# HTMD-PREAMP2.net
KiCad netlist of a schematic drawn in Altium Designer
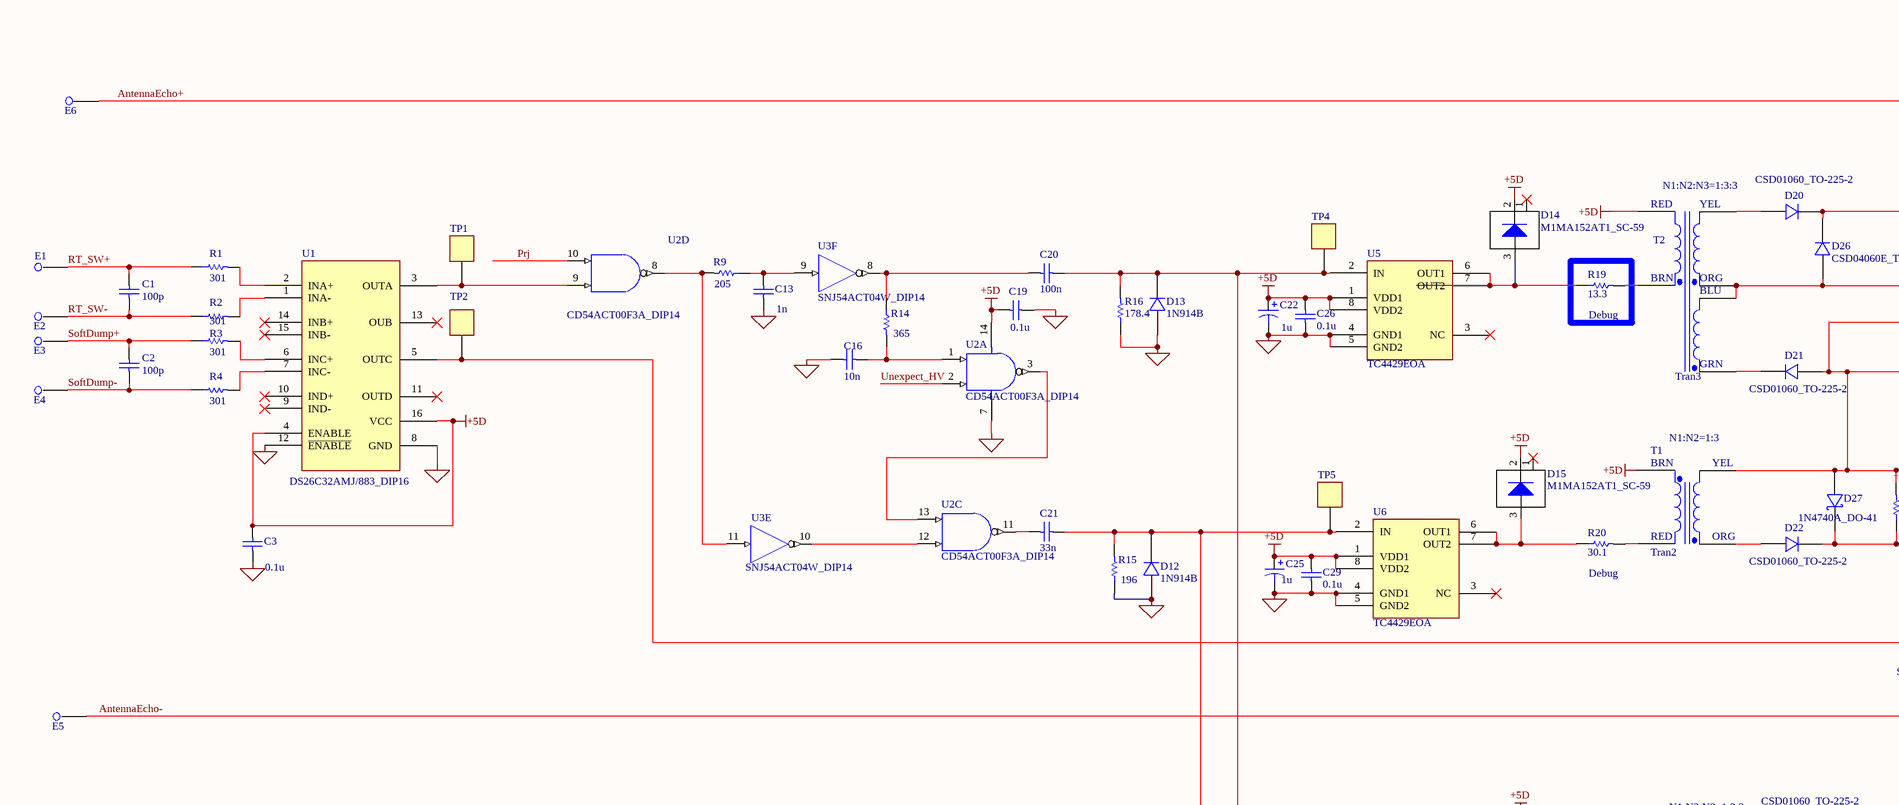
[diagram p0: HTMD-PREAMP2.SCHDOC, top left]
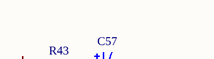
[diagram p1: HTMD-PREAMP2.SCHDOC, top right]
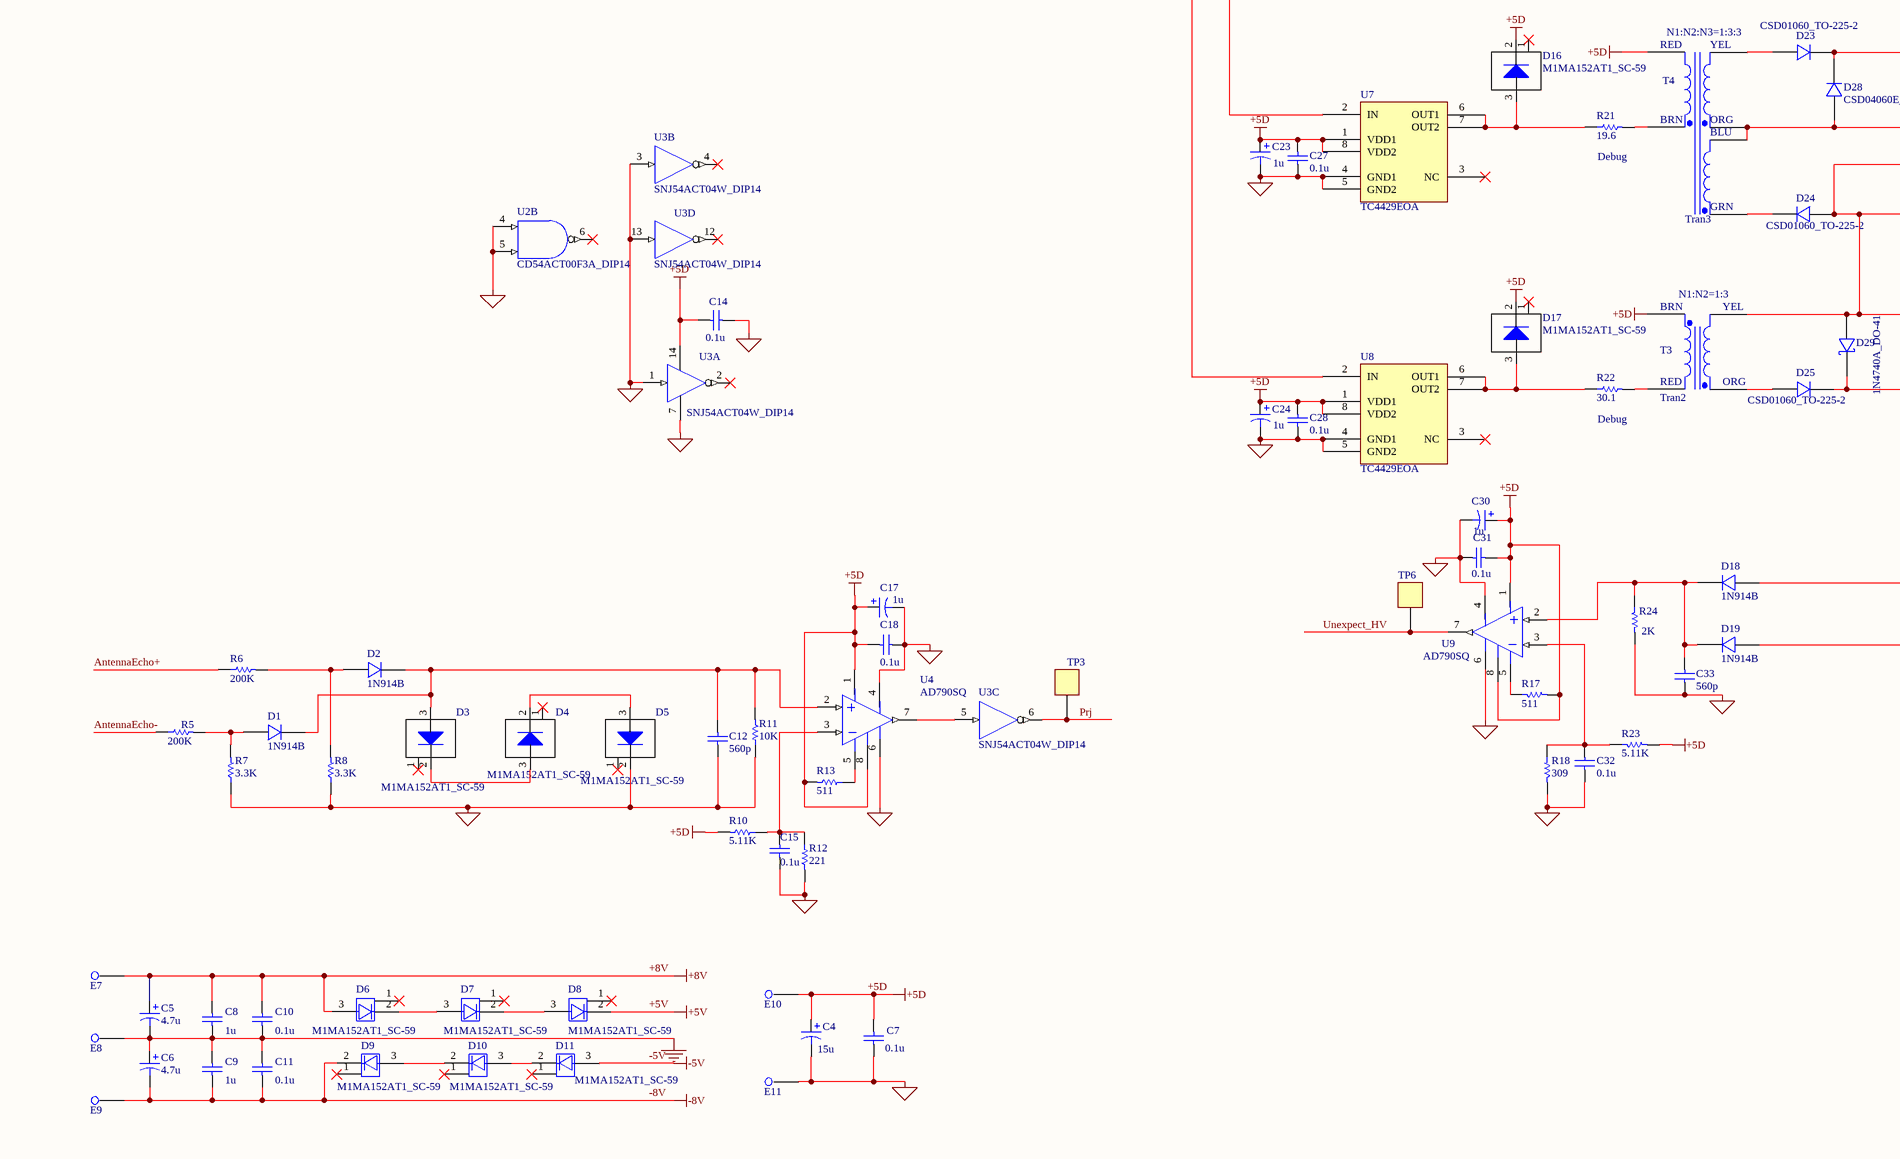
[diagram p2: HTMD-PREAMP2.SCHDOC, bottom left]
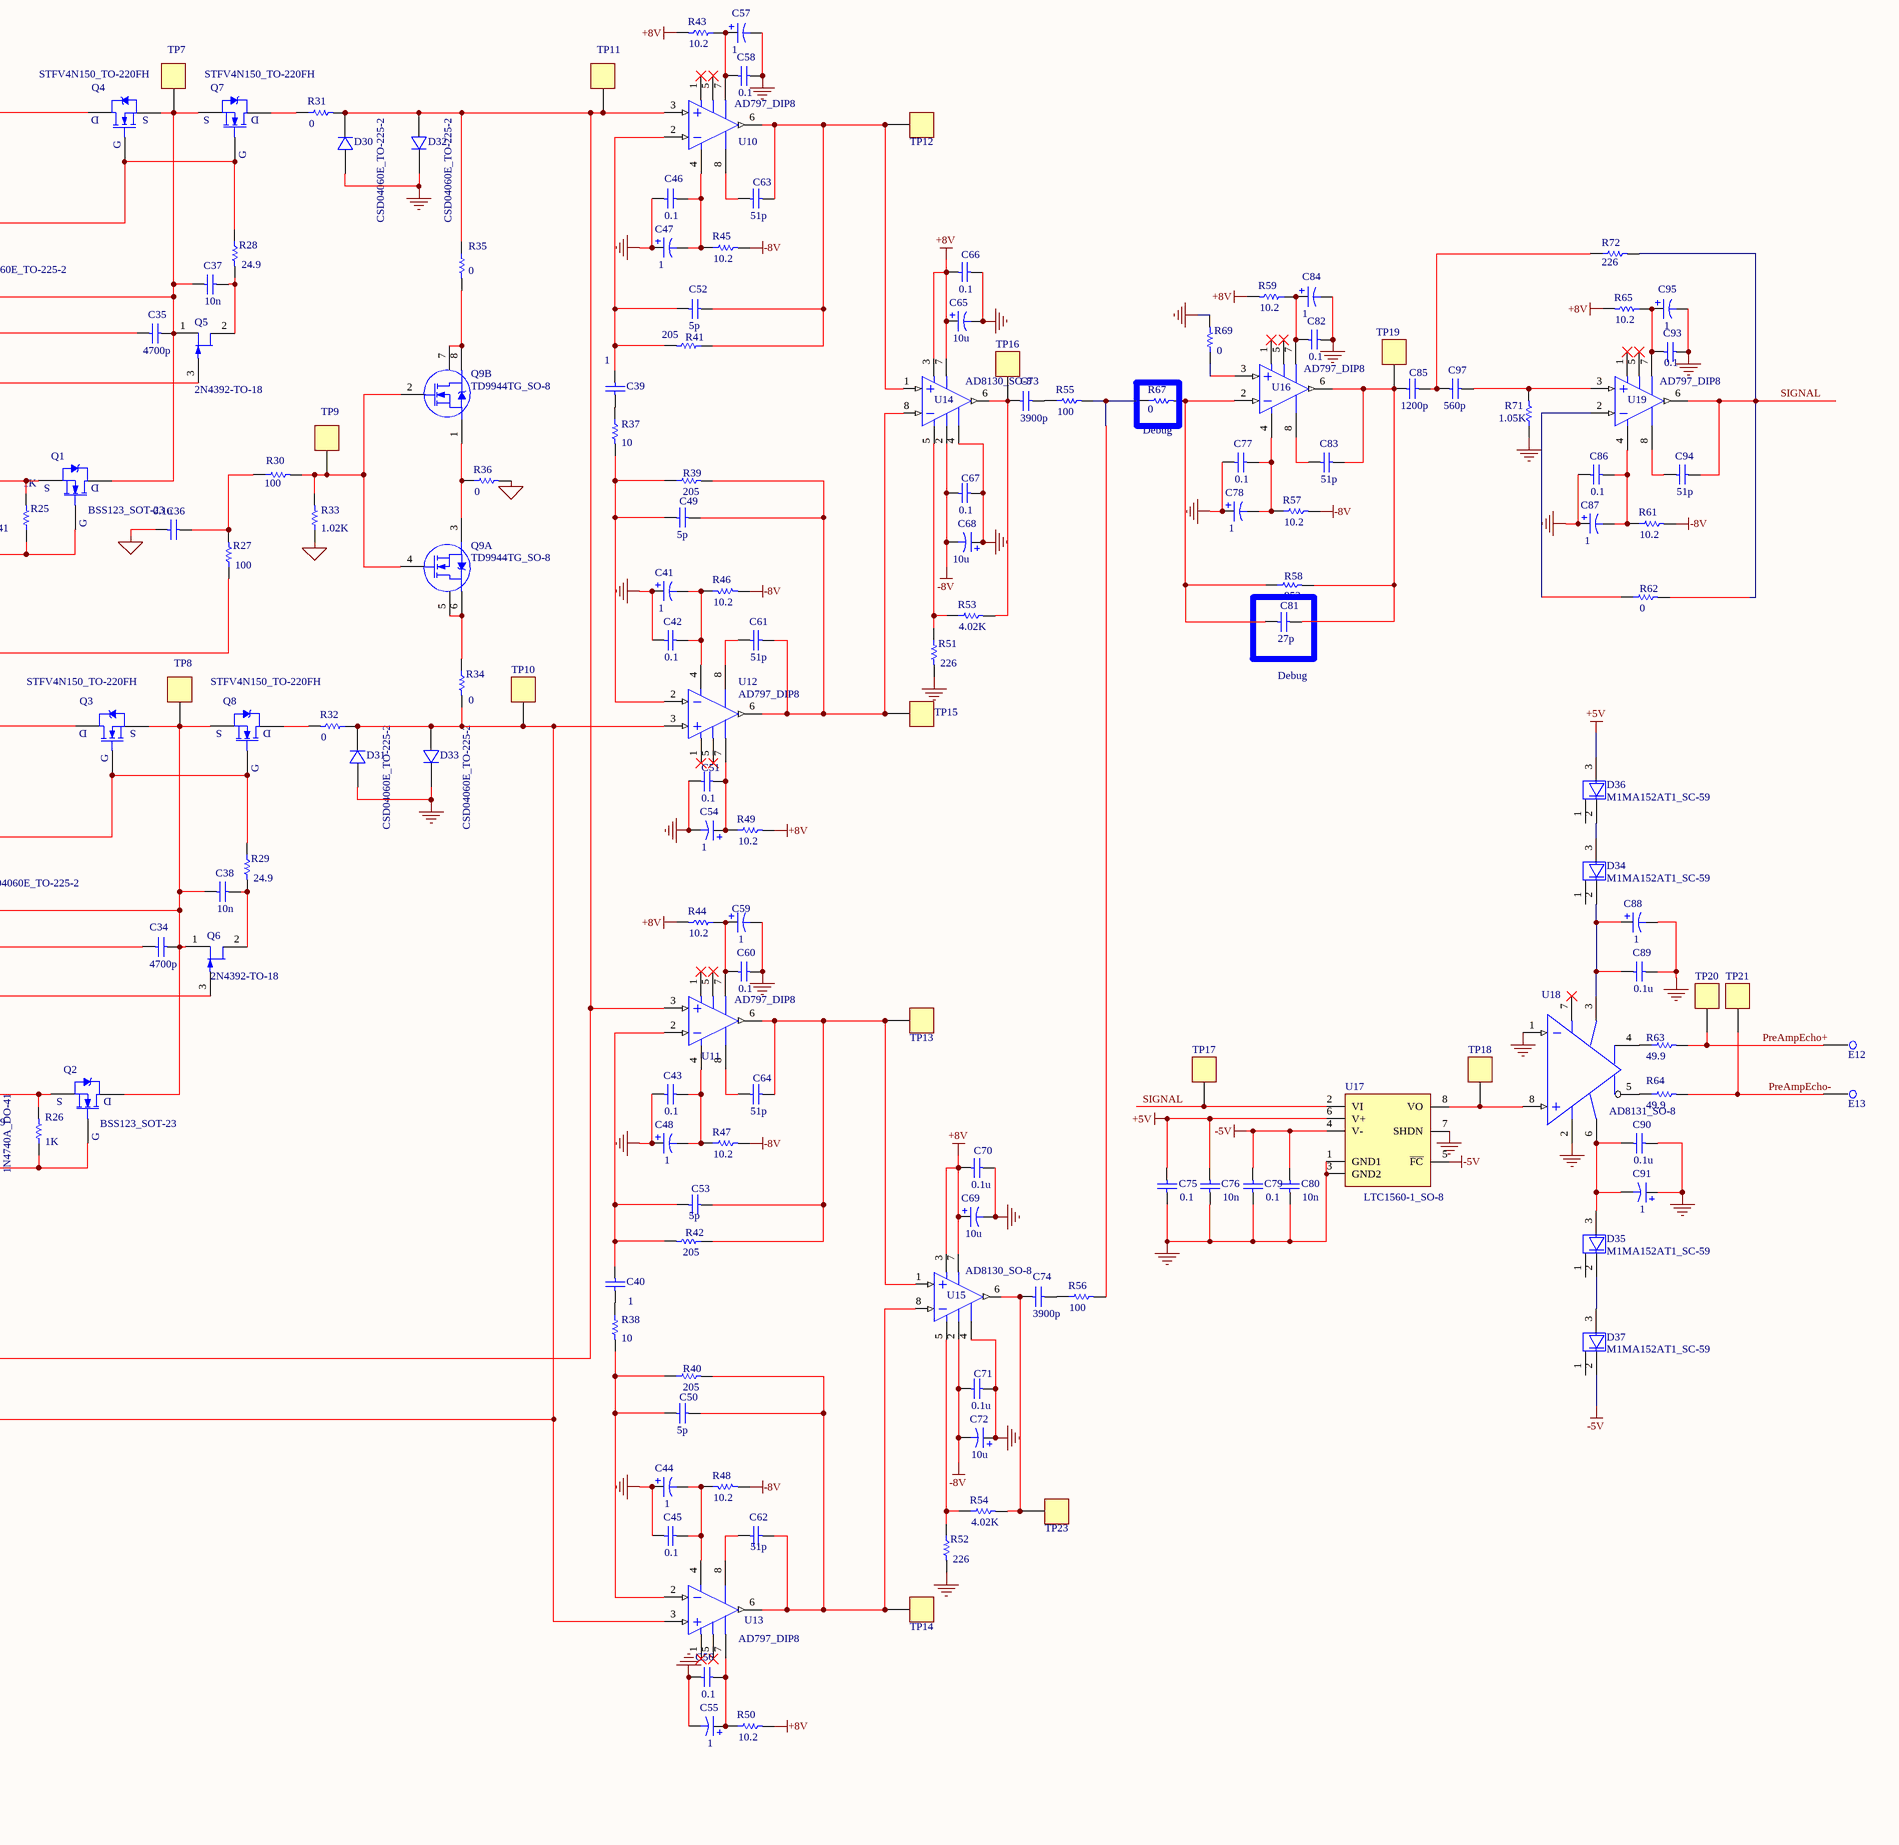
[diagram p3: HTMD-PREAMP2.SCHDOC, bottom right]

(export (version "E")
  (design (tool "Eeschema 10.0.6"))
  (components
    (comp (ref "C1")
      (value "100p")
      (footprint "C0805")
      (description "Capacitor")
      (fields (field (name "PUBLISHER") "Altium Limited"))
      (libsource (lib "*") (part "Cap"))
    )
    (comp (ref "C2")
      (value "100p")
      (footprint "C0805")
      (description "Capacitor")
      (fields (field (name "PUBLISHER") "Altium Limited"))
      (libsource (lib "*") (part "Cap"))
    )
    (comp (ref "C3")
      (value "0.1u")
      (footprint "C0805")
      (description "Capacitor")
      (fields (field (name "PUBLISHER") "Altium Limited"))
      (libsource (lib "*") (part "Cap"))
    )
    (comp (ref "C4")
      (value "15u")
      (footprint "595D")
      (description "Polarized Capacitor (Radial)")
      (fields (field (name "PUBLISHER") "Altium Limited"))
      (libsource (lib "*") (part "Cap Pol1"))
    )
    (comp (ref "C5")
      (value "4.7u")
      (footprint "595D")
      (description "Polarized Capacitor (Radial)")
      (fields (field (name "PUBLISHER") "Altium Limited"))
      (libsource (lib "*") (part "Cap Pol1"))
    )
    (comp (ref "C6")
      (value "4.7u")
      (footprint "595D")
      (description "Polarized Capacitor (Radial)")
      (fields (field (name "PUBLISHER") "Altium Limited"))
      (libsource (lib "*") (part "Cap Pol1"))
    )
    (comp (ref "C7")
      (value "0.1u")
      (footprint "C0805")
      (description "Capacitor")
      (fields (field (name "PUBLISHER") "Altium Limited"))
      (libsource (lib "*") (part "Cap"))
    )
    (comp (ref "C8")
      (value "1u")
      (footprint "1206")
      (description "Capacitor")
      (fields (field (name "PUBLISHER") "Altium Limited"))
      (libsource (lib "*") (part "Cap"))
    )
    (comp (ref "C9")
      (value "1u")
      (footprint "1206")
      (description "Capacitor")
      (fields (field (name "PUBLISHER") "Altium Limited"))
      (libsource (lib "*") (part "Cap"))
    )
    (comp (ref "C10")
      (value "0.1u")
      (footprint "C0805")
      (description "Capacitor")
      (fields (field (name "PUBLISHER") "Altium Limited"))
      (libsource (lib "*") (part "Cap"))
    )
    (comp (ref "C11")
      (value "0.1u")
      (footprint "C0805")
      (description "Capacitor")
      (fields (field (name "PUBLISHER") "Altium Limited"))
      (libsource (lib "*") (part "Cap"))
    )
    (comp (ref "C12")
      (value "560p")
      (footprint "C0805")
      (description "Capacitor")
      (fields (field (name "PUBLISHER") "Altium Limited"))
      (libsource (lib "Miscellaneous Devices") (part "Cap"))
    )
    (comp (ref "C13")
      (value "1n")
      (footprint "1206")
      (description "Capacitor")
      (fields (field (name "PUBLISHER") "Altium Limited"))
      (libsource (lib "*") (part "Cap"))
    )
    (comp (ref "C14")
      (value "0.1u")
      (footprint "C0805")
      (description "Capacitor")
      (fields (field (name "PUBLISHER") "Altium Limited"))
      (libsource (lib "*") (part "Cap"))
    )
    (comp (ref "C15")
      (value "0.1u")
      (footprint "C0805")
      (description "Capacitor")
      (fields (field (name "PUBLISHER") "Altium Limited"))
      (libsource (lib "*") (part "Cap"))
    )
    (comp (ref "C16")
      (value "10n")
      (footprint "C0805")
      (description "Capacitor")
      (fields (field (name "PUBLISHER") "Altium Limited"))
      (libsource (lib "*") (part "Cap"))
    )
    (comp (ref "C17")
      (value "1u")
      (footprint "C1206")
      (description "Polarized Capacitor (Radial)")
      (fields (field (name "PUBLISHER") "Altium Limited"))
      (libsource (lib "*") (part "Cap Pol1"))
    )
    (comp (ref "C18")
      (value "0.1u")
      (footprint "C0805")
      (description "Capacitor")
      (fields (field (name "PUBLISHER") "Altium Limited"))
      (libsource (lib "*") (part "Cap"))
    )
    (comp (ref "C19")
      (value "0.1u")
      (footprint "C0805")
      (description "Capacitor")
      (fields (field (name "PUBLISHER") "Altium Limited"))
      (libsource (lib "*") (part "Cap"))
    )
    (comp (ref "C20")
      (value "100n")
      (footprint "C0805")
      (description "Capacitor")
      (fields (field (name "PUBLISHER") "Altium Limited"))
      (libsource (lib "*") (part "Cap"))
    )
    (comp (ref "C21")
      (value "33n")
      (footprint "1206")
      (description "Capacitor")
      (fields (field (name "PUBLISHER") "Altium Limited"))
      (libsource (lib "*") (part "Cap"))
    )
    (comp (ref "C22")
      (value "1u")
      (footprint "C1206")
      (description "Polarized Capacitor (Radial)")
      (fields (field (name "PUBLISHER") "Altium Limited"))
      (libsource (lib "*") (part "Cap Pol1"))
    )
    (comp (ref "C23")
      (value "1u")
      (footprint "C1206")
      (description "Polarized Capacitor (Radial)")
      (fields (field (name "PUBLISHER") "Altium Limited"))
      (libsource (lib "*") (part "Cap Pol1"))
    )
    (comp (ref "C24")
      (value "1u")
      (footprint "C1206")
      (description "Polarized Capacitor (Radial)")
      (fields (field (name "PUBLISHER") "Altium Limited"))
      (libsource (lib "*") (part "Cap Pol1"))
    )
    (comp (ref "C25")
      (value "1u")
      (footprint "C1206")
      (description "Polarized Capacitor (Radial)")
      (fields (field (name "PUBLISHER") "Altium Limited"))
      (libsource (lib "*") (part "Cap Pol1"))
    )
    (comp (ref "C26")
      (value "0.1u")
      (footprint "C0805")
      (description "Capacitor")
      (fields (field (name "PUBLISHER") "Altium Limited"))
      (libsource (lib "*") (part "Cap"))
    )
    (comp (ref "C27")
      (value "0.1u")
      (footprint "C0805")
      (description "Capacitor")
      (fields (field (name "PUBLISHER") "Altium Limited"))
      (libsource (lib "*") (part "Cap"))
    )
    (comp (ref "C28")
      (value "0.1u")
      (footprint "C0805")
      (description "Capacitor")
      (fields (field (name "PUBLISHER") "Altium Limited"))
      (libsource (lib "*") (part "Cap"))
    )
    (comp (ref "C29")
      (value "0.1u")
      (footprint "C0805")
      (description "Capacitor")
      (fields (field (name "PUBLISHER") "Altium Limited"))
      (libsource (lib "*") (part "Cap"))
    )
    (comp (ref "C30")
      (value "1u")
      (footprint "C1206")
      (description "Polarized Capacitor (Radial)")
      (fields (field (name "PUBLISHER") "Altium Limited"))
      (libsource (lib "") (part "Cap Pol1_1"))
    )
    (comp (ref "C31")
      (value "0.1u")
      (footprint "C0805")
      (description "Capacitor")
      (fields (field (name "PUBLISHER") "Altium Limited"))
      (libsource (lib "*") (part "Cap"))
    )
    (comp (ref "C32")
      (value "0.1u")
      (footprint "C0805")
      (description "Capacitor")
      (fields (field (name "PUBLISHER") "Altium Limited"))
      (libsource (lib "*") (part "Cap"))
    )
    (comp (ref "C33")
      (value "560p")
      (footprint "C0805")
      (description "Capacitor")
      (fields (field (name "PUBLISHER") "Altium Limited"))
      (libsource (lib "*") (part "Cap"))
    )
    (comp (ref "C34")
      (value "4700p")
      (footprint "C0805")
      (description "Capacitor")
      (fields (field (name "PUBLISHER") "Altium Limited"))
      (libsource (lib "*") (part "Cap"))
    )
    (comp (ref "C35")
      (value "4700p")
      (footprint "C0805")
      (description "Capacitor")
      (fields (field (name "PUBLISHER") "Altium Limited"))
      (libsource (lib "*") (part "Cap"))
    )
    (comp (ref "C36")
      (value "0.1u")
      (footprint "C0805")
      (description "Capacitor")
      (fields (field (name "PUBLISHER") "Altium Limited"))
      (libsource (lib "*") (part "Cap"))
    )
    (comp (ref "C37")
      (value "10n")
      (footprint "1206")
      (description "Capacitor")
      (fields (field (name "PUBLISHER") "Altium Limited"))
      (libsource (lib "*") (part "Cap"))
    )
    (comp (ref "C38")
      (value "10n")
      (footprint "1206")
      (description "Capacitor")
      (fields (field (name "PUBLISHER") "Altium Limited"))
      (libsource (lib "*") (part "Cap"))
    )
    (comp (ref "C39")
      (value "1")
      (footprint "1206")
      (description "Capacitor")
      (fields (field (name "PUBLISHER") "Altium Limited"))
      (libsource (lib "*") (part "Cap"))
    )
    (comp (ref "C40")
      (value "1")
      (footprint "1206")
      (description "Capacitor")
      (fields (field (name "PUBLISHER") "Altium Limited"))
      (libsource (lib "*") (part "Cap"))
    )
    (comp (ref "C41")
      (value "1")
      (footprint "C1206")
      (description "Polarized Capacitor (Surface Mount)")
      (fields (field (name "PUBLISHER") "Altium Limited"))
      (libsource (lib "Miscellaneous Devices") (part "Cap Pol3"))
    )
    (comp (ref "C42")
      (value "0.1")
      (footprint "C0805")
      (description "Capacitor")
      (fields (field (name "PUBLISHER") "Altium Limited"))
      (libsource (lib "*") (part "Cap"))
    )
    (comp (ref "C43")
      (value "0.1")
      (footprint "C0805")
      (description "Capacitor")
      (fields (field (name "PUBLISHER") "Altium Limited"))
      (libsource (lib "*") (part "Cap"))
    )
    (comp (ref "C44")
      (value "1")
      (footprint "C1206")
      (description "Polarized Capacitor (Surface Mount)")
      (fields (field (name "PUBLISHER") "Altium Limited"))
      (libsource (lib "Miscellaneous Devices") (part "Cap Pol3"))
    )
    (comp (ref "C45")
      (value "0.1")
      (footprint "C0805")
      (description "Capacitor")
      (fields (field (name "PUBLISHER") "Altium Limited"))
      (libsource (lib "*") (part "Cap"))
    )
    (comp (ref "C46")
      (value "0.1")
      (footprint "C0805")
      (description "Capacitor")
      (fields (field (name "PUBLISHER") "Altium Limited"))
      (libsource (lib "*") (part "Cap"))
    )
    (comp (ref "C47")
      (value "1")
      (footprint "C1206")
      (description "Polarized Capacitor (Surface Mount)")
      (fields (field (name "PUBLISHER") "Altium Limited"))
      (libsource (lib "Miscellaneous Devices") (part "Cap Pol3"))
    )
    (comp (ref "C48")
      (value "1")
      (footprint "C1206")
      (description "Polarized Capacitor (Surface Mount)")
      (fields (field (name "PUBLISHER") "Altium Limited"))
      (libsource (lib "Miscellaneous Devices") (part "Cap Pol3"))
    )
    (comp (ref "C49")
      (value "5p")
      (footprint "C0805")
      (description "Capacitor")
      (fields (field (name "PUBLISHER") "Altium Limited"))
      (libsource (lib "*") (part "Cap"))
    )
    (comp (ref "C50")
      (value "5p")
      (footprint "C0805")
      (description "Capacitor")
      (fields (field (name "PUBLISHER") "Altium Limited"))
      (libsource (lib "*") (part "Cap"))
    )
    (comp (ref "C51")
      (value "0.1")
      (footprint "C0805")
      (description "Capacitor")
      (fields (field (name "PUBLISHER") "Altium Limited"))
      (libsource (lib "*") (part "Cap"))
    )
    (comp (ref "C52")
      (value "5p")
      (footprint "C0805")
      (description "Capacitor")
      (fields (field (name "PUBLISHER") "Altium Limited"))
      (libsource (lib "*") (part "Cap"))
    )
    (comp (ref "C53")
      (value "5p")
      (footprint "C0805")
      (description "Capacitor")
      (fields (field (name "PUBLISHER") "Altium Limited"))
      (libsource (lib "*") (part "Cap"))
    )
    (comp (ref "C54")
      (value "1")
      (footprint "C1206")
      (description "Polarized Capacitor (Surface Mount)")
      (fields (field (name "PUBLISHER") "Altium Limited"))
      (libsource (lib "Miscellaneous Devices") (part "Cap Pol3"))
    )
    (comp (ref "C55")
      (value "1")
      (footprint "C1206")
      (description "Polarized Capacitor (Surface Mount)")
      (fields (field (name "PUBLISHER") "Altium Limited"))
      (libsource (lib "Miscellaneous Devices") (part "Cap Pol3"))
    )
    (comp (ref "C56")
      (value "0.1")
      (footprint "C0805")
      (description "Capacitor")
      (fields (field (name "PUBLISHER") "Altium Limited"))
      (libsource (lib "*") (part "Cap"))
    )
    (comp (ref "C57")
      (value "1")
      (footprint "C1206")
      (description "Polarized Capacitor (Surface Mount)")
      (fields (field (name "PUBLISHER") "Altium Limited"))
      (libsource (lib "Miscellaneous Devices") (part "Cap Pol3"))
    )
    (comp (ref "C58")
      (value "0.1")
      (footprint "C0805")
      (description "Capacitor")
      (fields (field (name "PUBLISHER") "Altium Limited"))
      (libsource (lib "*") (part "Cap"))
    )
    (comp (ref "C59")
      (value "1")
      (footprint "C1206")
      (description "Polarized Capacitor (Surface Mount)")
      (fields (field (name "PUBLISHER") "Altium Limited"))
      (libsource (lib "Miscellaneous Devices") (part "Cap Pol3"))
    )
    (comp (ref "C60")
      (value "0.1")
      (footprint "C0805")
      (description "Capacitor")
      (fields (field (name "PUBLISHER") "Altium Limited"))
      (libsource (lib "*") (part "Cap"))
    )
    (comp (ref "C61")
      (value "51p")
      (footprint "C0805")
      (description "Capacitor")
      (fields (field (name "PUBLISHER") "Altium Limited"))
      (libsource (lib "*") (part "Cap"))
    )
    (comp (ref "C62")
      (value "51p")
      (footprint "C0805")
      (description "Capacitor")
      (fields (field (name "PUBLISHER") "Altium Limited"))
      (libsource (lib "*") (part "Cap"))
    )
    (comp (ref "C63")
      (value "51p")
      (footprint "C0805")
      (description "Capacitor")
      (fields (field (name "PUBLISHER") "Altium Limited"))
      (libsource (lib "*") (part "Cap"))
    )
    (comp (ref "C64")
      (value "51p")
      (footprint "C0805")
      (description "Capacitor")
      (fields (field (name "PUBLISHER") "Altium Limited"))
      (libsource (lib "*") (part "Cap"))
    )
    (comp (ref "C65")
      (value "10u")
      (footprint "7343")
      (description "Polarized Capacitor (Surface Mount)")
      (fields (field (name "PUBLISHER") "Altium Limited"))
      (libsource (lib "Miscellaneous Devices") (part "Cap Pol3"))
    )
    (comp (ref "C66")
      (value "0.1")
      (footprint "C0805")
      (description "Capacitor")
      (fields (field (name "PUBLISHER") "Altium Limited"))
      (libsource (lib "*") (part "Cap"))
    )
    (comp (ref "C67")
      (value "0.1")
      (footprint "C0805")
      (description "Capacitor")
      (fields (field (name "PUBLISHER") "Altium Limited"))
      (libsource (lib "*") (part "Cap"))
    )
    (comp (ref "C68")
      (value "10u")
      (footprint "7343")
      (description "Polarized Capacitor (Surface Mount)")
      (fields (field (name "PUBLISHER") "Altium Limited"))
      (libsource (lib "Miscellaneous Devices") (part "Cap Pol3"))
    )
    (comp (ref "C69")
      (value "10u")
      (footprint "7343")
      (description "Polarized Capacitor (Surface Mount)")
      (fields (field (name "PUBLISHER") "Altium Limited"))
      (libsource (lib "Miscellaneous Devices") (part "Cap Pol3"))
    )
    (comp (ref "C70")
      (value "0.1u")
      (footprint "C0805")
      (description "Capacitor")
      (fields (field (name "PUBLISHER") "Altium Limited"))
      (libsource (lib "*") (part "Cap"))
    )
    (comp (ref "C71")
      (value "0.1u")
      (footprint "C0805")
      (description "Capacitor")
      (fields (field (name "PUBLISHER") "Altium Limited"))
      (libsource (lib "*") (part "Cap"))
    )
    (comp (ref "C72")
      (value "10u")
      (footprint "7343")
      (description "Polarized Capacitor (Surface Mount)")
      (fields (field (name "PUBLISHER") "Altium Limited"))
      (libsource (lib "Miscellaneous Devices") (part "Cap Pol3"))
    )
    (comp (ref "C73")
      (value "3900p")
      (footprint "1206")
      (description "Capacitor")
      (fields (field (name "PUBLISHER") "Altium Limited"))
      (libsource (lib "*") (part "Cap"))
    )
    (comp (ref "C74")
      (value "3900p")
      (footprint "1206")
      (description "Capacitor")
      (fields (field (name "PUBLISHER") "Altium Limited"))
      (libsource (lib "*") (part "Cap"))
    )
    (comp (ref "C75")
      (value "0.1")
      (footprint "C0805")
      (description "Capacitor")
      (fields (field (name "PUBLISHER") "Altium Limited"))
      (libsource (lib "*") (part "Cap"))
    )
    (comp (ref "C76")
      (value "10n")
      (footprint "C0805")
      (description "Capacitor")
      (fields (field (name "PUBLISHER") "Altium Limited"))
      (libsource (lib "*") (part "Cap"))
    )
    (comp (ref "C77")
      (value "0.1")
      (footprint "C0805")
      (description "Capacitor")
      (fields (field (name "PUBLISHER") "Altium Limited"))
      (libsource (lib "*") (part "Cap"))
    )
    (comp (ref "C78")
      (value "1")
      (footprint "C1206")
      (description "Polarized Capacitor (Surface Mount)")
      (fields (field (name "PUBLISHER") "Altium Limited"))
      (libsource (lib "Miscellaneous Devices") (part "Cap Pol3"))
    )
    (comp (ref "C79")
      (value "0.1")
      (footprint "C0805")
      (description "Capacitor")
      (fields (field (name "PUBLISHER") "Altium Limited"))
      (libsource (lib "*") (part "Cap"))
    )
    (comp (ref "C80")
      (value "10n")
      (footprint "C0805")
      (description "Capacitor")
      (fields (field (name "PUBLISHER") "Altium Limited"))
      (libsource (lib "*") (part "Cap"))
    )
    (comp (ref "C81")
      (value "27p")
      (footprint "C0805")
      (description "Capacitor")
      (fields (field (name "PUBLISHER") "Altium Limited"))
      (libsource (lib "*") (part "Cap"))
    )
    (comp (ref "C82")
      (value "0.1")
      (footprint "C0805")
      (description "Capacitor")
      (fields (field (name "PUBLISHER") "Altium Limited"))
      (libsource (lib "*") (part "Cap"))
    )
    (comp (ref "C83")
      (value "51p")
      (footprint "C0805")
      (description "Capacitor")
      (fields (field (name "PUBLISHER") "Altium Limited"))
      (libsource (lib "*") (part "Cap"))
    )
    (comp (ref "C84")
      (value "1")
      (footprint "C1206")
      (description "Polarized Capacitor (Surface Mount)")
      (fields (field (name "PUBLISHER") "Altium Limited"))
      (libsource (lib "Miscellaneous Devices") (part "Cap Pol3"))
    )
    (comp (ref "C85")
      (value "1200p")
      (footprint "C0805")
      (description "Capacitor")
      (fields (field (name "PUBLISHER") "Altium Limited"))
      (libsource (lib "*") (part "Cap"))
    )
    (comp (ref "C86")
      (value "0.1")
      (footprint "C0805")
      (description "Capacitor")
      (fields (field (name "PUBLISHER") "Altium Limited"))
      (libsource (lib "*") (part "Cap"))
    )
    (comp (ref "C87")
      (value "1")
      (footprint "C1206")
      (description "Polarized Capacitor (Surface Mount)")
      (fields (field (name "PUBLISHER") "Altium Limited"))
      (libsource (lib "Miscellaneous Devices") (part "Cap Pol3"))
    )
    (comp (ref "C88")
      (value "1")
      (footprint "C1206")
      (description "Polarized Capacitor (Surface Mount)")
      (fields (field (name "PUBLISHER") "Altium Limited"))
      (libsource (lib "Miscellaneous Devices") (part "Cap Pol3"))
    )
    (comp (ref "C89")
      (value "0.1u")
      (footprint "C0805")
      (description "Capacitor")
      (fields (field (name "PUBLISHER") "Altium Limited"))
      (libsource (lib "*") (part "Cap"))
    )
    (comp (ref "C90")
      (value "0.1u")
      (footprint "C0805")
      (description "Capacitor")
      (fields (field (name "PUBLISHER") "Altium Limited"))
      (libsource (lib "*") (part "Cap"))
    )
    (comp (ref "C91")
      (value "1")
      (footprint "C1206")
      (description "Polarized Capacitor (Surface Mount)")
      (fields (field (name "PUBLISHER") "Altium Limited"))
      (libsource (lib "Miscellaneous Devices") (part "Cap Pol3"))
    )
    (comp (ref "C93")
      (value "0.1")
      (footprint "C0805")
      (description "Capacitor")
      (fields (field (name "PUBLISHER") "Altium Limited"))
      (libsource (lib "*") (part "Cap"))
    )
    (comp (ref "C94")
      (value "51p")
      (footprint "C0805")
      (description "Capacitor")
      (fields (field (name "PUBLISHER") "Altium Limited"))
      (libsource (lib "*") (part "Cap"))
    )
    (comp (ref "C95")
      (value "1")
      (footprint "C1206")
      (description "Polarized Capacitor (Surface Mount)")
      (fields (field (name "PUBLISHER") "Altium Limited"))
      (libsource (lib "Miscellaneous Devices") (part "Cap Pol3"))
    )
    (comp (ref "C97")
      (value "560p")
      (footprint "C0805")
      (description "Capacitor")
      (fields (field (name "PUBLISHER") "Altium Limited"))
      (libsource (lib "Miscellaneous Devices") (part "Cap"))
    )
    (comp (ref "D1") (value "1N914B") (footprint "DO-35") (libsource (lib "*") (part "1N914B")))
    (comp (ref "D2") (value "1N914B") (footprint "DO-35") (libsource (lib "*") (part "1N914B")))
    (comp (ref "D3")
      (value "M1MA152AT1_SC-59")
      (footprint "SC-59")
      (description "single silicon switching diodes")
      (fields (field (name "PUBLISHER") "Altium Limited"))
      (libsource (lib "") (part "M1MA152AT1_1"))
    )
    (comp (ref "D4")
      (value "M1MA152AT1_SC-59")
      (footprint "SC-59")
      (description "single silicon switching diodes")
      (fields (field (name "PUBLISHER") "Altium Limited"))
      (libsource (lib "") (part "M1MA152AT1_1"))
    )
    (comp (ref "D5")
      (value "M1MA152AT1_SC-59")
      (footprint "SC-59")
      (description "single silicon switching diodes")
      (fields (field (name "PUBLISHER") "Altium Limited"))
      (libsource (lib "") (part "M1MA152AT1_1"))
    )
    (comp (ref "D6") (value "M1MA152AT1_SC-59") (footprint "SC-59") (libsource (lib "*") (part "M1MA152AT1")))
    (comp (ref "D7") (value "M1MA152AT1_SC-59") (footprint "SC-59") (libsource (lib "*") (part "M1MA152AT1")))
    (comp (ref "D8") (value "M1MA152AT1_SC-59") (footprint "SC-59") (libsource (lib "*") (part "M1MA152AT1")))
    (comp (ref "D9") (value "M1MA152AT1_SC-59") (footprint "SC-59") (libsource (lib "*") (part "M1MA152AT1")))
    (comp (ref "D10")
      (value "M1MA152AT1_SC-59")
      (footprint "SC-59")
      (libsource (lib "*") (part "M1MA152AT1"))
    )
    (comp (ref "D11")
      (value "M1MA152AT1_SC-59")
      (footprint "SC-59")
      (libsource (lib "*") (part "M1MA152AT1"))
    )
    (comp (ref "D12") (value "1N914B") (footprint "DO-35") (libsource (lib "*") (part "1N914B")))
    (comp (ref "D13") (value "1N914B") (footprint "DO-35") (libsource (lib "*") (part "1N914B")))
    (comp (ref "D14")
      (value "M1MA152AT1_SC-59")
      (footprint "SC-59")
      (description "single silicon switching diodes")
      (fields (field (name "PUBLISHER") "Altium Limited"))
      (libsource (lib "*") (part "M1MA152AT1_1"))
    )
    (comp (ref "D15")
      (value "M1MA152AT1_SC-59")
      (footprint "SC-59")
      (description "single silicon switching diodes")
      (fields (field (name "PUBLISHER") "Altium Limited"))
      (libsource (lib "*") (part "M1MA152AT1_1"))
    )
    (comp (ref "D16")
      (value "M1MA152AT1_SC-59")
      (footprint "SC-59")
      (description "single silicon switching diodes")
      (fields (field (name "PUBLISHER") "Altium Limited"))
      (libsource (lib "*") (part "M1MA152AT1_1"))
    )
    (comp (ref "D17")
      (value "M1MA152AT1_SC-59")
      (footprint "SC-59")
      (description "single silicon switching diodes")
      (fields (field (name "PUBLISHER") "Altium Limited"))
      (libsource (lib "*") (part "M1MA152AT1_1"))
    )
    (comp (ref "D18") (value "1N914B") (footprint "DO-35") (libsource (lib "*") (part "1N914B")))
    (comp (ref "D19") (value "1N914B") (footprint "DO-35") (libsource (lib "*") (part "1N914B")))
    (comp (ref "D20")
      (value "CSD01060_TO-225-2")
      (footprint "TO-225-2")
      (description "CSD01060")
      (libsource (lib "*") (part "CSD01060"))
    )
    (comp (ref "D21")
      (value "CSD01060_TO-225-2")
      (footprint "TO-225-2")
      (description "CSD01060")
      (libsource (lib "*") (part "CSD01060"))
    )
    (comp (ref "D22")
      (value "CSD01060_TO-225-2")
      (footprint "TO-225-2")
      (description "CSD01060")
      (libsource (lib "*") (part "CSD01060"))
    )
    (comp (ref "D23")
      (value "CSD01060_TO-225-2")
      (footprint "TO-225-2")
      (description "CSD01060")
      (libsource (lib "*") (part "CSD01060"))
    )
    (comp (ref "D24")
      (value "CSD01060_TO-225-2")
      (footprint "TO-225-2")
      (description "CSD01060")
      (libsource (lib "*") (part "CSD01060"))
    )
    (comp (ref "D25")
      (value "CSD01060_TO-225-2")
      (footprint "TO-225-2")
      (description "CSD01060")
      (libsource (lib "*") (part "CSD01060"))
    )
    (comp (ref "D26")
      (value "CSD04060E_TO-225-2")
      (footprint "TO-225-2")
      (description "CSD04060E")
      (libsource (lib "*") (part "CSD04060E"))
    )
    (comp (ref "D27")
      (value "1N4740A_DO-41")
      (footprint "DO-41")
      (description "Schottky Rectifier")
      (libsource (lib "*") (part "1N4740A"))
    )
    (comp (ref "D28")
      (value "CSD04060E_TO-225-2")
      (footprint "TO-225-2")
      (description "CSD04060E")
      (libsource (lib "*") (part "CSD04060E"))
    )
    (comp (ref "D29")
      (value "1N4740A_DO-41")
      (footprint "DO-41")
      (description "Schottky Rectifier")
      (libsource (lib "*") (part "1N4740A"))
    )
    (comp (ref "D30")
      (value "CSD04060E_TO-225-2")
      (footprint "TO-225-2")
      (description "CSD04060E")
      (libsource (lib "*") (part "CSD04060E"))
    )
    (comp (ref "D31")
      (value "CSD04060E_TO-225-2")
      (footprint "TO-225-2")
      (description "CSD04060E")
      (libsource (lib "*") (part "CSD04060E"))
    )
    (comp (ref "D32")
      (value "CSD04060E_TO-225-2")
      (footprint "TO-225-2")
      (description "CSD04060E")
      (libsource (lib "*") (part "CSD04060E"))
    )
    (comp (ref "D33")
      (value "CSD04060E_TO-225-2")
      (footprint "TO-225-2")
      (description "CSD04060E")
      (libsource (lib "*") (part "CSD04060E"))
    )
    (comp (ref "D34")
      (value "M1MA152AT1_SC-59")
      (footprint "SC-59")
      (libsource (lib "*") (part "M1MA152AT1"))
    )
    (comp (ref "D35")
      (value "M1MA152AT1_SC-59")
      (footprint "SC-59")
      (libsource (lib "*") (part "M1MA152AT1"))
    )
    (comp (ref "D36")
      (value "M1MA152AT1_SC-59")
      (footprint "SC-59")
      (libsource (lib "*") (part "M1MA152AT1"))
    )
    (comp (ref "D37")
      (value "M1MA152AT1_SC-59")
      (footprint "SC-59")
      (libsource (lib "*") (part "M1MA152AT1"))
    )
    (comp (ref "E1") (value "InOut") (footprint "TermSignal") (libsource (lib "PreAmp") (part "InOut")))
    (comp (ref "E2") (value "InOut") (footprint "TermSignal") (libsource (lib "*") (part "InOut")))
    (comp (ref "E3") (value "InOut") (footprint "TermSignal") (libsource (lib "*") (part "InOut")))
    (comp (ref "E4") (value "InOut") (footprint "TermSignal") (libsource (lib "*") (part "InOut")))
    (comp (ref "E5") (value "InOut") (footprint "TermSignal") (libsource (lib "*") (part "InOut")))
    (comp (ref "E6") (value "InOut") (footprint "TermSignal") (libsource (lib "*") (part "InOut")))
    (comp (ref "E7") (value "InOut") (footprint "TermPower") (libsource (lib "*") (part "InOut")))
    (comp (ref "E8") (value "InOut") (footprint "TermPower") (libsource (lib "*") (part "InOut")))
    (comp (ref "E9") (value "InOut") (footprint "TermPower") (libsource (lib "*") (part "InOut")))
    (comp (ref "E10") (value "InOut") (footprint "TermPower") (libsource (lib "*") (part "InOut")))
    (comp (ref "E11") (value "InOut") (footprint "TermPower") (libsource (lib "*") (part "InOut")))
    (comp (ref "E12") (value "InOut") (footprint "TermSignal") (libsource (lib "*") (part "InOut")))
    (comp (ref "E13") (value "InOut") (footprint "TermSignal") (libsource (lib "*") (part "InOut")))
    (comp (ref "Q1")
      (value "BSS123_SOT-23")
      (footprint "SOT-23")
      (description "BSS123")
      (libsource (lib "*") (part "BSS123"))
    )
    (comp (ref "Q2")
      (value "BSS123_SOT-23")
      (footprint "SOT-23")
      (description "BSS123")
      (libsource (lib "*") (part "BSS123"))
    )
    (comp (ref "Q3")
      (value "STFV4N150_TO-220FH")
      (footprint "TO-220FH")
      (libsource (lib "*") (part "STFV4N150"))
    )
    (comp (ref "Q4")
      (value "STFV4N150_TO-220FH")
      (footprint "TO-220FH")
      (libsource (lib "*") (part "STFV4N150"))
    )
    (comp (ref "Q5") (value "2N4392-TO-18") (footprint "TO-18") (libsource (lib "*") (part "MPF4392")))
    (comp (ref "Q6") (value "2N4392-TO-18") (footprint "TO-18") (libsource (lib "*") (part "MPF4392")))
    (comp (ref "Q7")
      (value "STFV4N150_TO-220FH")
      (footprint "TO-220FH")
      (libsource (lib "*") (part "STFV4N150"))
    )
    (comp (ref "Q8")
      (value "STFV4N150_TO-220FH")
      (footprint "TO-220FH")
      (libsource (lib "*") (part "STFV4N150"))
    )
    (comp (ref "Q9") (value "TD9944TG_SO-8") (footprint "SO-8") (libsource (lib "") (part "TD9944_1")))
    (comp (ref "R1")
      (value "301")
      (footprint "R0805")
      (description "Resistor")
      (fields (field (name "PUBLISHER") "Altium Limited"))
      (libsource (lib "*") (part "Res1"))
    )
    (comp (ref "R2")
      (value "301")
      (footprint "R0805")
      (description "Resistor")
      (fields (field (name "PUBLISHER") "Altium Limited"))
      (libsource (lib "*") (part "Res1"))
    )
    (comp (ref "R3")
      (value "301")
      (footprint "R0805")
      (description "Resistor")
      (fields (field (name "PUBLISHER") "Altium Limited"))
      (libsource (lib "*") (part "Res1"))
    )
    (comp (ref "R4")
      (value "301")
      (footprint "R0805")
      (description "Resistor")
      (fields (field (name "PUBLISHER") "Altium Limited"))
      (libsource (lib "*") (part "Res1"))
    )
    (comp (ref "R5")
      (value "200K")
      (footprint "MG680")
      (description "Resistor")
      (fields (field (name "PUBLISHER") "Altium Limited"))
      (libsource (lib "*") (part "Res1"))
    )
    (comp (ref "R6")
      (value "200K")
      (footprint "MG680")
      (description "Resistor")
      (fields (field (name "PUBLISHER") "Altium Limited"))
      (libsource (lib "*") (part "Res1"))
    )
    (comp (ref "R7")
      (value "3.3K")
      (footprint "2010")
      (description "Resistor")
      (fields (field (name "PUBLISHER") "Altium Limited"))
      (libsource (lib "*") (part "Res1"))
    )
    (comp (ref "R8")
      (value "3.3K")
      (footprint "2010")
      (description "Resistor")
      (fields (field (name "PUBLISHER") "Altium Limited"))
      (libsource (lib "*") (part "Res1"))
    )
    (comp (ref "R9")
      (value "205")
      (footprint "R0805")
      (description "Resistor")
      (fields (field (name "PUBLISHER") "Altium Limited"))
      (libsource (lib "*") (part "Res1"))
    )
    (comp (ref "R10")
      (value "5.11K")
      (footprint "R0805")
      (description "Resistor")
      (fields (field (name "PUBLISHER") "Altium Limited"))
      (libsource (lib "*") (part "Res1"))
    )
    (comp (ref "R11")
      (value "10K")
      (footprint "R1206")
      (description "Resistor")
      (fields (field (name "PUBLISHER") "Altium Limited"))
      (libsource (lib "*") (part "Res1"))
    )
    (comp (ref "R12")
      (value "221")
      (footprint "R0805")
      (description "Resistor")
      (fields (field (name "PUBLISHER") "Altium Limited"))
      (libsource (lib "*") (part "Res1"))
    )
    (comp (ref "R13")
      (value "511")
      (footprint "R0805")
      (description "Resistor")
      (fields (field (name "PUBLISHER") "Altium Limited"))
      (libsource (lib "*") (part "Res1"))
    )
    (comp (ref "R14")
      (value "365")
      (footprint "R0805")
      (description "Resistor")
      (fields (field (name "PUBLISHER") "Altium Limited"))
      (libsource (lib "*") (part "Res1"))
    )
    (comp (ref "R15")
      (value "196")
      (footprint "R0805")
      (description "Resistor")
      (fields (field (name "PUBLISHER") "Altium Limited"))
      (libsource (lib "*") (part "Res1"))
    )
    (comp (ref "R16")
      (value "178.4")
      (footprint "R0805")
      (description "Resistor")
      (fields (field (name "PUBLISHER") "Altium Limited"))
      (libsource (lib "*") (part "Res1"))
    )
    (comp (ref "R17")
      (value "511")
      (footprint "R0805")
      (description "Resistor")
      (fields (field (name "PUBLISHER") "Altium Limited"))
      (libsource (lib "*") (part "Res1"))
    )
    (comp (ref "R18")
      (value "309")
      (footprint "R0805")
      (description "Resistor")
      (fields (field (name "PUBLISHER") "Altium Limited"))
      (libsource (lib "*") (part "Res1"))
    )
    (comp (ref "R19")
      (value "13.3")
      (footprint "R0805")
      (description "Resistor")
      (fields (field (name "PUBLISHER") "Altium Limited"))
      (libsource (lib "*") (part "Res1"))
    )
    (comp (ref "R20")
      (value "30.1")
      (footprint "R0805")
      (description "Resistor")
      (fields (field (name "PUBLISHER") "Altium Limited"))
      (libsource (lib "*") (part "Res1"))
    )
    (comp (ref "R21")
      (value "19.6")
      (footprint "R0805")
      (description "Resistor")
      (fields (field (name "PUBLISHER") "Altium Limited"))
      (libsource (lib "*") (part "Res1"))
    )
    (comp (ref "R22")
      (value "30.1")
      (footprint "R0805")
      (description "Resistor")
      (fields (field (name "PUBLISHER") "Altium Limited"))
      (libsource (lib "*") (part "Res1"))
    )
    (comp (ref "R23")
      (value "5.11K")
      (footprint "R0805")
      (description "Resistor")
      (fields (field (name "PUBLISHER") "Altium Limited"))
      (libsource (lib "*") (part "Res1"))
    )
    (comp (ref "R24")
      (value "2K")
      (footprint "R1206")
      (description "Resistor")
      (fields (field (name "PUBLISHER") "Altium Limited"))
      (libsource (lib "*") (part "Res1"))
    )
    (comp (ref "R25")
      (value "1K")
      (footprint "R0805")
      (description "Resistor")
      (fields (field (name "PUBLISHER") "Altium Limited"))
      (libsource (lib "*") (part "Res1"))
    )
    (comp (ref "R26")
      (value "1K")
      (footprint "R0805")
      (description "Resistor")
      (fields (field (name "PUBLISHER") "Altium Limited"))
      (libsource (lib "*") (part "Res1"))
    )
    (comp (ref "R27")
      (value "100")
      (footprint "R0805")
      (description "Resistor")
      (fields (field (name "PUBLISHER") "Altium Limited"))
      (libsource (lib "*") (part "Res1"))
    )
    (comp (ref "R28")
      (value "24.9")
      (footprint "R0805")
      (description "Resistor")
      (fields (field (name "PUBLISHER") "Altium Limited"))
      (libsource (lib "*") (part "Res1"))
    )
    (comp (ref "R29")
      (value "24.9")
      (footprint "R0805")
      (description "Resistor")
      (fields (field (name "PUBLISHER") "Altium Limited"))
      (libsource (lib "*") (part "Res1"))
    )
    (comp (ref "R30")
      (value "100")
      (footprint "R0805")
      (description "Resistor")
      (fields (field (name "PUBLISHER") "Altium Limited"))
      (libsource (lib "*") (part "Res1"))
    )
    (comp (ref "R31")
      (value "0")
      (footprint "R0805")
      (description "Resistor")
      (fields (field (name "PUBLISHER") "Altium Limited"))
      (libsource (lib "*") (part "Res1"))
    )
    (comp (ref "R32")
      (value "0")
      (footprint "R0805")
      (description "Resistor")
      (fields (field (name "PUBLISHER") "Altium Limited"))
      (libsource (lib "*") (part "Res1"))
    )
    (comp (ref "R33")
      (value "1.02K")
      (footprint "R0805")
      (description "Resistor")
      (fields (field (name "PUBLISHER") "Altium Limited"))
      (libsource (lib "*") (part "Res1"))
    )
    (comp (ref "R34")
      (value "0")
      (footprint "R0805")
      (description "Resistor")
      (fields (field (name "PUBLISHER") "Altium Limited"))
      (libsource (lib "*") (part "Res1"))
    )
    (comp (ref "R35")
      (value "0")
      (footprint "R0805")
      (description "Resistor")
      (fields (field (name "PUBLISHER") "Altium Limited"))
      (libsource (lib "*") (part "Res1"))
    )
    (comp (ref "R36")
      (value "0")
      (footprint "R0805")
      (description "Resistor")
      (fields (field (name "PUBLISHER") "Altium Limited"))
      (libsource (lib "*") (part "Res1"))
    )
    (comp (ref "R37")
      (value "10")
      (footprint "R0805")
      (description "Resistor")
      (fields (field (name "PUBLISHER") "Altium Limited"))
      (libsource (lib "*") (part "Res1"))
    )
    (comp (ref "R38")
      (value "10")
      (footprint "R0805")
      (description "Resistor")
      (fields (field (name "PUBLISHER") "Altium Limited"))
      (libsource (lib "*") (part "Res1"))
    )
    (comp (ref "R39")
      (value "205")
      (footprint "R0805")
      (description "Resistor")
      (fields (field (name "PUBLISHER") "Altium Limited"))
      (libsource (lib "*") (part "Res1"))
    )
    (comp (ref "R40")
      (value "205")
      (footprint "R0805")
      (description "Resistor")
      (fields (field (name "PUBLISHER") "Altium Limited"))
      (libsource (lib "*") (part "Res1"))
    )
    (comp (ref "R41")
      (value "205")
      (footprint "R0805")
      (description "Resistor")
      (fields (field (name "PUBLISHER") "Altium Limited"))
      (libsource (lib "*") (part "Res1"))
    )
    (comp (ref "R42")
      (value "205")
      (footprint "R0805")
      (description "Resistor")
      (fields (field (name "PUBLISHER") "Altium Limited"))
      (libsource (lib "*") (part "Res1"))
    )
    (comp (ref "R43")
      (value "10.2")
      (footprint "R0805")
      (description "Resistor")
      (fields (field (name "PUBLISHER") "Altium Limited"))
      (libsource (lib "*") (part "Res1"))
    )
    (comp (ref "R44")
      (value "10.2")
      (footprint "R0805")
      (description "Resistor")
      (fields (field (name "PUBLISHER") "Altium Limited"))
      (libsource (lib "*") (part "Res1"))
    )
    (comp (ref "R45")
      (value "10.2")
      (footprint "R0805")
      (description "Resistor")
      (fields (field (name "PUBLISHER") "Altium Limited"))
      (libsource (lib "*") (part "Res1"))
    )
    (comp (ref "R46")
      (value "10.2")
      (footprint "R0805")
      (description "Resistor")
      (fields (field (name "PUBLISHER") "Altium Limited"))
      (libsource (lib "*") (part "Res1"))
    )
    (comp (ref "R47")
      (value "10.2")
      (footprint "R0805")
      (description "Resistor")
      (fields (field (name "PUBLISHER") "Altium Limited"))
      (libsource (lib "*") (part "Res1"))
    )
    (comp (ref "R48")
      (value "10.2")
      (footprint "R0805")
      (description "Resistor")
      (fields (field (name "PUBLISHER") "Altium Limited"))
      (libsource (lib "*") (part "Res1"))
    )
    (comp (ref "R49")
      (value "10.2")
      (footprint "R0805")
      (description "Resistor")
      (fields (field (name "PUBLISHER") "Altium Limited"))
      (libsource (lib "*") (part "Res1"))
    )
    (comp (ref "R50")
      (value "10.2")
      (footprint "R0805")
      (description "Resistor")
      (fields (field (name "PUBLISHER") "Altium Limited"))
      (libsource (lib "*") (part "Res1"))
    )
    (comp (ref "R51")
      (value "226")
      (footprint "R0805")
      (description "Resistor")
      (fields (field (name "PUBLISHER") "Altium Limited"))
      (libsource (lib "*") (part "Res1"))
    )
    (comp (ref "R52")
      (value "226")
      (footprint "R0805")
      (description "Resistor")
      (fields (field (name "PUBLISHER") "Altium Limited"))
      (libsource (lib "*") (part "Res1"))
    )
    (comp (ref "R53")
      (value "4.02K")
      (footprint "R0805")
      (description "Resistor")
      (fields (field (name "PUBLISHER") "Altium Limited"))
      (libsource (lib "*") (part "Res1"))
    )
    (comp (ref "R54")
      (value "4.02K")
      (footprint "R0805")
      (description "Resistor")
      (fields (field (name "PUBLISHER") "Altium Limited"))
      (libsource (lib "*") (part "Res1"))
    )
    (comp (ref "R55")
      (value "100")
      (footprint "R0805")
      (description "Resistor")
      (fields (field (name "PUBLISHER") "Altium Limited"))
      (libsource (lib "*") (part "Res1"))
    )
    (comp (ref "R56")
      (value "100")
      (footprint "R0805")
      (description "Resistor")
      (fields (field (name "PUBLISHER") "Altium Limited"))
      (libsource (lib "*") (part "Res1"))
    )
    (comp (ref "R57")
      (value "10.2")
      (footprint "R0805")
      (description "Resistor")
      (fields (field (name "PUBLISHER") "Altium Limited"))
      (libsource (lib "*") (part "Res1"))
    )
    (comp (ref "R58")
      (value "953")
      (footprint "R0805")
      (description "Resistor")
      (fields (field (name "PUBLISHER") "Altium Limited"))
      (libsource (lib "*") (part "Res1"))
    )
    (comp (ref "R59")
      (value "10.2")
      (footprint "R0805")
      (description "Resistor")
      (fields (field (name "PUBLISHER") "Altium Limited"))
      (libsource (lib "") (part "Res1_1"))
    )
    (comp (ref "R61")
      (value "10.2")
      (footprint "R0805")
      (description "Resistor")
      (fields (field (name "PUBLISHER") "Altium Limited"))
      (libsource (lib "*") (part "Res1"))
    )
    (comp (ref "R62")
      (value "0")
      (footprint "R0805")
      (description "Resistor")
      (fields (field (name "PUBLISHER") "Altium Limited"))
      (libsource (lib "*") (part "Res1"))
    )
    (comp (ref "R63")
      (value "49.9")
      (footprint "R0805")
      (description "Resistor")
      (fields (field (name "PUBLISHER") "Altium Limited"))
      (libsource (lib "*") (part "Res1"))
    )
    (comp (ref "R64")
      (value "49.9")
      (footprint "R0805")
      (description "Resistor")
      (fields (field (name "PUBLISHER") "Altium Limited"))
      (libsource (lib "*") (part "Res1"))
    )
    (comp (ref "R65")
      (value "10.2")
      (footprint "R0805")
      (description "Resistor")
      (fields (field (name "PUBLISHER") "Altium Limited"))
      (libsource (lib "") (part "Res1_1"))
    )
    (comp (ref "R67")
      (value "0")
      (footprint "R0805")
      (description "Resistor")
      (fields (field (name "PUBLISHER") "Altium Limited"))
      (libsource (lib "Miscellaneous Devices") (part "Res1"))
    )
    (comp (ref "R69")
      (value "0")
      (footprint "R0805")
      (description "Resistor")
      (fields (field (name "PUBLISHER") "Altium Limited"))
      (libsource (lib "Miscellaneous Devices") (part "Res1"))
    )
    (comp (ref "R71")
      (value "1.05K")
      (footprint "R0805")
      (description "Resistor")
      (fields (field (name "PUBLISHER") "Altium Limited"))
      (libsource (lib "Miscellaneous Devices") (part "Res1"))
    )
    (comp (ref "R72")
      (value "226")
      (footprint "R0805")
      (description "Resistor")
      (fields (field (name "PUBLISHER") "Altium Limited"))
      (libsource (lib "Miscellaneous Devices") (part "Res1"))
    )
    (comp (ref "T1") (value "Tran2") (footprint "Tran2") (libsource (lib "*") (part "Tran2")))
    (comp (ref "T2") (value "Tran3") (footprint "Tran3") (libsource (lib "*") (part "Tran3")))
    (comp (ref "T3") (value "Tran2") (footprint "Tran2") (libsource (lib "*") (part "Tran2")))
    (comp (ref "T4") (value "Tran3") (footprint "Tran3") (libsource (lib "*") (part "Tran3")))
    (comp (ref "TP1") (value "TestPoint") (footprint "test_small") (libsource (lib "*") (part "TestPoint")))
    (comp (ref "TP2") (value "TestPoint") (footprint "test_small") (libsource (lib "*") (part "TestPoint")))
    (comp (ref "TP3") (value "TestPoint") (footprint "test_small") (libsource (lib "*") (part "TestPoint")))
    (comp (ref "TP4") (value "TestPoint") (footprint "test_small") (libsource (lib "*") (part "TestPoint")))
    (comp (ref "TP5") (value "TestPoint") (footprint "test_small") (libsource (lib "*") (part "TestPoint")))
    (comp (ref "TP6") (value "TestPoint") (footprint "test_small") (libsource (lib "") (part "TestPoint_1")))
    (comp (ref "TP7") (value "TestPoint") (footprint "test_small") (libsource (lib "*") (part "TestPoint")))
    (comp (ref "TP8") (value "TestPoint") (footprint "test_small") (libsource (lib "*") (part "TestPoint")))
    (comp (ref "TP9") (value "TestPoint") (footprint "test_small") (libsource (lib "*") (part "TestPoint")))
    (comp (ref "TP10") (value "TestPoint") (footprint "test_small") (libsource (lib "*") (part "TestPoint")))
    (comp (ref "TP11") (value "TestPoint") (footprint "test_small") (libsource (lib "*") (part "TestPoint")))
    (comp (ref "TP12") (value "TestPoint") (footprint "test_small") (libsource (lib "") (part "TestPoint_1")))
    (comp (ref "TP13") (value "TestPoint") (footprint "test_small") (libsource (lib "") (part "TestPoint_1")))
    (comp (ref "TP14") (value "TestPoint") (footprint "test_small") (libsource (lib "") (part "TestPoint_1")))
    (comp (ref "TP15") (value "TestPoint") (footprint "test_small") (libsource (lib "") (part "TestPoint_1")))
    (comp (ref "TP16") (value "TestPoint") (footprint "test_small") (libsource (lib "*") (part "TestPoint")))
    (comp (ref "TP17") (value "TestPoint") (footprint "test_small") (libsource (lib "*") (part "TestPoint")))
    (comp (ref "TP18") (value "TestPoint") (footprint "test_small") (libsource (lib "*") (part "TestPoint")))
    (comp (ref "TP19") (value "TestPoint") (footprint "test_small") (libsource (lib "*") (part "TestPoint")))
    (comp (ref "TP20") (value "TestPoint") (footprint "test_small") (libsource (lib "*") (part "TestPoint")))
    (comp (ref "TP21") (value "TestPoint") (footprint "test_small") (libsource (lib "*") (part "TestPoint")))
    (comp (ref "TP23") (value "TestPoint") (footprint "test_small") (libsource (lib "") (part "TestPoint_1")))
    (comp (ref "U1")
      (value "DS26C32AMJ/883_DIP16")
      (footprint "DIP16")
      (libsource (lib "*") (part "DS26LV32AM"))
    )
    (comp (ref "U2")
      (value "CD54ACT00F3A_DIP14")
      (footprint "DIP14")
      (libsource (lib "PreAmp") (part "SNJ54ACT00W"))
    )
    (comp (ref "U3")
      (value "SNJ54ACT04W_DIP14")
      (footprint "DIP14")
      (description "Hex Inverter")
      (libsource (lib "PreAmp") (part "SNJ54ACT04W"))
    )
    (comp (ref "U4")
      (value "AD790SQ")
      (footprint "DIP8")
      (description "fast,precision comparator")
      (fields (field (name "PUBLISHER") "Altium Limited"))
      (libsource (lib "AD Operational Amplifier") (part "AD790SQ"))
    )
    (comp (ref "U5") (value "TC4429EOA") (footprint "SO-8") (libsource (lib "*") (part "TC4429EOA")))
    (comp (ref "U6") (value "TC4429EOA") (footprint "SO-8") (libsource (lib "*") (part "TC4429EOA")))
    (comp (ref "U7") (value "TC4429EOA") (footprint "SO-8") (libsource (lib "*") (part "TC4429EOA")))
    (comp (ref "U8") (value "TC4429EOA") (footprint "SO-8") (libsource (lib "*") (part "TC4429EOA")))
    (comp (ref "U9")
      (value "AD790SQ")
      (footprint "DIP8")
      (description "fast,precision comparator")
      (fields (field (name "PUBLISHER") "Altium Limited"))
      (libsource (lib "AD Operational Amplifier") (part "AD790SQ"))
    )
    (comp (ref "U10") (value "AD797_DIP8") (footprint "DIP8") (libsource (lib "*") (part "AD797")))
    (comp (ref "U11") (value "AD797_DIP8") (footprint "DIP8") (libsource (lib "*") (part "AD797")))
    (comp (ref "U12") (value "AD797_DIP8") (footprint "DIP8") (libsource (lib "*") (part "AD797")))
    (comp (ref "U13") (value "AD797_DIP8") (footprint "DIP8") (libsource (lib "*") (part "AD797")))
    (comp (ref "U14") (value "AD8130_SO-8") (footprint "SO-8") (libsource (lib "*") (part "AD8130")))
    (comp (ref "U15") (value "AD8130_SO-8") (footprint "SO-8") (libsource (lib "*") (part "AD8130")))
    (comp (ref "U16") (value "AD797_DIP8") (footprint "DIP8") (libsource (lib "*") (part "AD797")))
    (comp (ref "U17") (value "LTC1560-1_SO-8") (footprint "SO-8") (libsource (lib "*") (part "LTC1560")))
    (comp (ref "U18") (value "AD8131_SO-8") (footprint "SO-8") (libsource (lib "*") (part "AD8131")))
    (comp (ref "U19") (value "AD797_DIP8") (footprint "DIP8") (libsource (lib "*") (part "AD797")))
  )
  (nets
    (net (code "1") (name "+5D") (class "Default")
      (node (ref "C14") (pin "2") (pinfunction "2_2") (pintype "passive"))
      (node (ref "C17") (pin "1") (pinfunction "1_1") (pintype "passive"))
      (node (ref "C18") (pin "1") (pinfunction "1_1") (pintype "passive"))
      (node (ref "C19") (pin "2") (pinfunction "2_2") (pintype "passive"))
      (node (ref "C22") (pin "1") (pinfunction "1_1") (pintype "passive"))
      (node (ref "C23") (pin "1") (pinfunction "1_1") (pintype "passive"))
      (node (ref "C24") (pin "1") (pinfunction "1_1") (pintype "passive"))
      (node (ref "C25") (pin "1") (pinfunction "1_1") (pintype "passive"))
      (node (ref "C26") (pin "2") (pinfunction "2_2") (pintype "passive"))
      (node (ref "C27") (pin "2") (pinfunction "2_2") (pintype "passive"))
      (node (ref "C28") (pin "2") (pinfunction "2_2") (pintype "passive"))
      (node (ref "C29") (pin "2") (pinfunction "2_2") (pintype "passive"))
      (node (ref "C3") (pin "1") (pinfunction "1_1") (pintype "passive"))
      (node (ref "C30") (pin "1") (pinfunction "1_1") (pintype "passive"))
      (node (ref "C31") (pin "1") (pinfunction "1_1") (pintype "passive"))
      (node (ref "C4") (pin "1") (pinfunction "1_1") (pintype "passive"))
      (node (ref "C7") (pin "2") (pinfunction "2_2") (pintype "passive"))
      (node (ref "D14") (pin "2") (pintype "passive"))
      (node (ref "D15") (pin "2") (pintype "passive"))
      (node (ref "D16") (pin "2") (pintype "passive"))
      (node (ref "D17") (pin "2") (pintype "passive"))
      (node (ref "E10") (pin "1") (pinfunction "NC_1") (pintype "passive"))
      (node (ref "R10") (pin "2") (pinfunction "2_2") (pintype "passive"))
      (node (ref "R13") (pin "2") (pinfunction "2_2") (pintype "passive"))
      (node (ref "R17") (pin "2") (pinfunction "2_2") (pintype "passive"))
      (node (ref "R23") (pin "2") (pinfunction "2_2") (pintype "passive"))
      (node (ref "T1") (pin "4") (pinfunction "Pri-_4") (pintype "passive"))
      (node (ref "T2") (pin "6") (pinfunction "Pri+_6") (pintype "passive"))
      (node (ref "T3") (pin "4") (pinfunction "Pri-_4") (pintype "passive"))
      (node (ref "T4") (pin "6") (pinfunction "Pri+_6") (pintype "passive"))
      (node (ref "U1") (pin "16") (pinfunction "VCC_16") (pintype "passive"))
      (node (ref "U1") (pin "4") (pinfunction "ENABLE_4") (pintype "passive"))
      (node (ref "U2") (pin "14") (pinfunction "Vcc_14") (pintype "power_in"))
      (node (ref "U3") (pin "14") (pinfunction "Vcc_14") (pintype "power_in"))
      (node (ref "U4") (pin "1") (pinfunction "+Vs_1") (pintype "power_in"))
      (node (ref "U4") (pin "8") (pinfunction "Vlogic_8") (pintype "passive"))
      (node (ref "U5") (pin "1") (pinfunction "VDD1_1") (pintype "passive"))
      (node (ref "U5") (pin "8") (pinfunction "VDD2_8") (pintype "passive"))
      (node (ref "U6") (pin "1") (pinfunction "VDD1_1") (pintype "passive"))
      (node (ref "U6") (pin "8") (pinfunction "VDD2_8") (pintype "passive"))
      (node (ref "U7") (pin "1") (pinfunction "VDD1_1") (pintype "passive"))
      (node (ref "U7") (pin "8") (pinfunction "VDD2_8") (pintype "passive"))
      (node (ref "U8") (pin "1") (pinfunction "VDD1_1") (pintype "passive"))
      (node (ref "U8") (pin "8") (pinfunction "VDD2_8") (pintype "passive"))
      (node (ref "U9") (pin "1") (pinfunction "+Vs_1") (pintype "power_in"))
      (node (ref "U9") (pin "8") (pinfunction "Vlogic_8") (pintype "passive"))
    )
    (net (code "2") (name "+5V") (class "Default")
      (node (ref "C75") (pin "1") (pinfunction "1_1") (pintype "passive"))
      (node (ref "C76") (pin "1") (pinfunction "1_1") (pintype "passive"))
      (node (ref "D36") (pin "3") (pinfunction "A_3") (pintype "passive"))
      (node (ref "D8") (pin "2") (pinfunction "K_2") (pintype "passive"))
      (node (ref "U17") (pin "6") (pinfunction "V+_6") (pintype "passive"))
    )
    (net (code "3") (name "+8V") (class "Default")
      (node (ref "C10") (pin "1") (pinfunction "1_1") (pintype "passive"))
      (node (ref "C5") (pin "1") (pinfunction "1_1") (pintype "passive"))
      (node (ref "C65") (pin "1") (pinfunction "1_1") (pintype "passive"))
      (node (ref "C66") (pin "2") (pinfunction "2_2") (pintype "passive"))
      (node (ref "C69") (pin "1") (pinfunction "1_1") (pintype "passive"))
      (node (ref "C70") (pin "2") (pinfunction "2_2") (pintype "passive"))
      (node (ref "C8") (pin "1") (pinfunction "1_1") (pintype "passive"))
      (node (ref "D6") (pin "3") (pinfunction "A_3") (pintype "passive"))
      (node (ref "E7") (pin "1") (pinfunction "NC_1") (pintype "passive"))
      (node (ref "R43") (pin "2") (pinfunction "2_2") (pintype "passive"))
      (node (ref "R44") (pin "2") (pinfunction "2_2") (pintype "passive"))
      (node (ref "R49") (pin "2") (pinfunction "2_2") (pintype "passive"))
      (node (ref "R50") (pin "2") (pinfunction "2_2") (pintype "passive"))
      (node (ref "R59") (pin "2") (pinfunction "2_2") (pintype "passive"))
      (node (ref "R65") (pin "2") (pinfunction "2_2") (pintype "passive"))
      (node (ref "U14") (pin "3") (pinfunction "~{PD}_3") (pintype "power_in"))
      (node (ref "U14") (pin "7") (pinfunction "+VS_7") (pintype "power_in"))
      (node (ref "U15") (pin "3") (pinfunction "~{PD}_3") (pintype "power_in"))
      (node (ref "U15") (pin "7") (pinfunction "+VS_7") (pintype "power_in"))
    )
    (net (code "4") (name "-5V") (class "Default")
      (node (ref "C79") (pin "1") (pinfunction "1_1") (pintype "passive"))
      (node (ref "C80") (pin "1") (pinfunction "1_1") (pintype "passive"))
      (node (ref "D11") (pin "3") (pinfunction "A_3") (pintype "passive"))
      (node (ref "D37") (pin "2") (pinfunction "K_2") (pintype "passive"))
      (node (ref "U17") (pin "4") (pinfunction "V-_4") (pintype "passive"))
      (node (ref "U17") (pin "5") (pinfunction "~{FC}_5") (pintype "passive"))
    )
    (net (code "5") (name "-8V") (class "Default")
      (node (ref "C11") (pin "1") (pinfunction "1_1") (pintype "passive"))
      (node (ref "C6") (pin "2") (pinfunction "2_2") (pintype "passive"))
      (node (ref "C67") (pin "2") (pinfunction "2_2") (pintype "passive"))
      (node (ref "C68") (pin "2") (pinfunction "2_2") (pintype "passive"))
      (node (ref "C71") (pin "2") (pinfunction "2_2") (pintype "passive"))
      (node (ref "C72") (pin "2") (pinfunction "2_2") (pintype "passive"))
      (node (ref "C9") (pin "2") (pinfunction "2_2") (pintype "passive"))
      (node (ref "D9") (pin "2") (pinfunction "K_2") (pintype "passive"))
      (node (ref "E9") (pin "1") (pinfunction "NC_1") (pintype "passive"))
      (node (ref "R45") (pin "2") (pinfunction "2_2") (pintype "passive"))
      (node (ref "R46") (pin "2") (pinfunction "2_2") (pintype "passive"))
      (node (ref "R47") (pin "2") (pinfunction "2_2") (pintype "passive"))
      (node (ref "R48") (pin "2") (pinfunction "2_2") (pintype "passive"))
      (node (ref "R57") (pin "2") (pinfunction "2_2") (pintype "passive"))
      (node (ref "R61") (pin "2") (pinfunction "2_2") (pintype "passive"))
      (node (ref "U14") (pin "2") (pinfunction "-VS_2") (pintype "power_in"))
      (node (ref "U15") (pin "2") (pinfunction "-VS_2") (pintype "power_in"))
    )
    (net (code "6") (name "/AntennaEcho+") (class "Default")
      (node (ref "E6") (pin "1") (pinfunction "NC_1") (pintype "passive"))
      (node (ref "Q4") (pin "2") (pinfunction "D_2") (pintype "passive"))
      (node (ref "R6") (pin "1") (pinfunction "1_1") (pintype "passive"))
    )
    (net (code "7") (name "/AntennaEcho-") (class "Default")
      (node (ref "E5") (pin "1") (pinfunction "NC_1") (pintype "passive"))
      (node (ref "Q3") (pin "2") (pinfunction "D_2") (pintype "passive"))
      (node (ref "R5") (pin "1") (pinfunction "1_1") (pintype "passive"))
    )
    (net (code "8") (name "/PreAmpEcho+") (class "Default")
      (node (ref "E12") (pin "1") (pinfunction "NC_1") (pintype "passive"))
      (node (ref "R63") (pin "2") (pinfunction "2_2") (pintype "passive"))
      (node (ref "TP20") (pin "1") (pinfunction "NC_1") (pintype "passive"))
    )
    (net (code "9") (name "/PreAmpEcho-") (class "Default")
      (node (ref "E13") (pin "1") (pinfunction "NC_1") (pintype "passive"))
      (node (ref "R64") (pin "2") (pinfunction "2_2") (pintype "passive"))
      (node (ref "TP21") (pin "1") (pinfunction "NC_1") (pintype "passive"))
    )
    (net (code "10") (name "/Prj") (class "Default")
      (node (ref "TP3") (pin "1") (pinfunction "NC_1") (pintype "passive"))
      (node (ref "U2") (pin "10") (pinfunction "A_10") (pintype "input"))
      (node (ref "U3") (pin "6") (pinfunction "~{O}_6") (pintype "output"))
    )
    (net (code "11") (name "/RT_SW+") (class "Default")
      (node (ref "C1") (pin "2") (pinfunction "2_2") (pintype "passive"))
      (node (ref "E1") (pin "1") (pinfunction "NC_1") (pintype "passive"))
      (node (ref "R1") (pin "1") (pinfunction "1_1") (pintype "passive"))
    )
    (net (code "12") (name "/RT_SW-") (class "Default")
      (node (ref "C1") (pin "1") (pinfunction "1_1") (pintype "passive"))
      (node (ref "E2") (pin "1") (pinfunction "NC_1") (pintype "passive"))
      (node (ref "R2") (pin "1") (pinfunction "1_1") (pintype "passive"))
    )
    (net (code "13") (name "/SIGNAL") (class "Default")
      (node (ref "C94") (pin "1") (pinfunction "1_1") (pintype "passive"))
      (node (ref "R62") (pin "2") (pinfunction "2_2") (pintype "passive"))
      (node (ref "R72") (pin "2") (pinfunction "2_2") (pintype "passive"))
      (node (ref "TP17") (pin "1") (pinfunction "NC_1") (pintype "passive"))
      (node (ref "U17") (pin "2") (pinfunction "VI_2") (pintype "passive"))
      (node (ref "U19") (pin "6") (pinfunction "OUTPUT_6") (pintype "output"))
    )
    (net (code "14") (name "/SoftDump+") (class "Default")
      (node (ref "C2") (pin "2") (pinfunction "2_2") (pintype "passive"))
      (node (ref "E3") (pin "1") (pinfunction "NC_1") (pintype "passive"))
      (node (ref "R3") (pin "1") (pinfunction "1_1") (pintype "passive"))
    )
    (net (code "15") (name "/SoftDump-") (class "Default")
      (node (ref "C2") (pin "1") (pinfunction "1_1") (pintype "passive"))
      (node (ref "E4") (pin "1") (pinfunction "NC_1") (pintype "passive"))
      (node (ref "R4") (pin "1") (pinfunction "1_1") (pintype "passive"))
    )
    (net (code "16") (name "/Unexpect_HV") (class "Default")
      (node (ref "TP6") (pin "1") (pinfunction "NC_1") (pintype "passive"))
      (node (ref "U2") (pin "2") (pinfunction "B_2") (pintype "input"))
      (node (ref "U9") (pin "7") (pinfunction "OUT_7") (pintype "output"))
    )
    (net (code "17") (name "AGND") (class "Default")
      (node (ref "C10") (pin "2") (pinfunction "2_2") (pintype "passive"))
      (node (ref "C11") (pin "2") (pinfunction "2_2") (pintype "passive"))
      (node (ref "C41") (pin "1") (pinfunction "1_1") (pintype "passive"))
      (node (ref "C42") (pin "1") (pinfunction "1_1") (pintype "passive"))
      (node (ref "C43") (pin "1") (pinfunction "1_1") (pintype "passive"))
      (node (ref "C44") (pin "1") (pinfunction "1_1") (pintype "passive"))
      (node (ref "C45") (pin "2") (pinfunction "2_2") (pintype "passive"))
      (node (ref "C46") (pin "1") (pinfunction "1_1") (pintype "passive"))
      (node (ref "C47") (pin "1") (pinfunction "1_1") (pintype "passive"))
      (node (ref "C48") (pin "1") (pinfunction "1_1") (pintype "passive"))
      (node (ref "C5") (pin "2") (pinfunction "2_2") (pintype "passive"))
      (node (ref "C51") (pin "2") (pinfunction "2_2") (pintype "passive"))
      (node (ref "C54") (pin "2") (pinfunction "2_2") (pintype "passive"))
      (node (ref "C55") (pin "2") (pinfunction "2_2") (pintype "passive"))
      (node (ref "C56") (pin "2") (pinfunction "2_2") (pintype "passive"))
      (node (ref "C57") (pin "2") (pinfunction "2_2") (pintype "passive"))
      (node (ref "C58") (pin "2") (pinfunction "2_2") (pintype "passive"))
      (node (ref "C59") (pin "2") (pinfunction "2_2") (pintype "passive"))
      (node (ref "C6") (pin "1") (pinfunction "1_1") (pintype "passive"))
      (node (ref "C60") (pin "2") (pinfunction "2_2") (pintype "passive"))
      (node (ref "C65") (pin "2") (pinfunction "2_2") (pintype "passive"))
      (node (ref "C66") (pin "1") (pinfunction "1_1") (pintype "passive"))
      (node (ref "C67") (pin "1") (pinfunction "1_1") (pintype "passive"))
      (node (ref "C68") (pin "1") (pinfunction "1_1") (pintype "passive"))
      (node (ref "C69") (pin "2") (pinfunction "2_2") (pintype "passive"))
      (node (ref "C70") (pin "1") (pinfunction "1_1") (pintype "passive"))
      (node (ref "C71") (pin "1") (pinfunction "1_1") (pintype "passive"))
      (node (ref "C72") (pin "1") (pinfunction "1_1") (pintype "passive"))
      (node (ref "C75") (pin "2") (pinfunction "2_2") (pintype "passive"))
      (node (ref "C76") (pin "2") (pinfunction "2_2") (pintype "passive"))
      (node (ref "C77") (pin "1") (pinfunction "1_1") (pintype "passive"))
      (node (ref "C78") (pin "1") (pinfunction "1_1") (pintype "passive"))
      (node (ref "C79") (pin "2") (pinfunction "2_2") (pintype "passive"))
      (node (ref "C8") (pin "2") (pinfunction "2_2") (pintype "passive"))
      (node (ref "C80") (pin "2") (pinfunction "2_2") (pintype "passive"))
      (node (ref "C82") (pin "2") (pinfunction "2_2") (pintype "passive"))
      (node (ref "C84") (pin "2") (pinfunction "2_2") (pintype "passive"))
      (node (ref "C86") (pin "1") (pinfunction "1_1") (pintype "passive"))
      (node (ref "C87") (pin "1") (pinfunction "1_1") (pintype "passive"))
      (node (ref "C88") (pin "2") (pinfunction "2_2") (pintype "passive"))
      (node (ref "C89") (pin "2") (pinfunction "2_2") (pintype "passive"))
      (node (ref "C9") (pin "1") (pinfunction "1_1") (pintype "passive"))
      (node (ref "C90") (pin "1") (pinfunction "1_1") (pintype "passive"))
      (node (ref "C91") (pin "1") (pinfunction "1_1") (pintype "passive"))
      (node (ref "C93") (pin "2") (pinfunction "2_2") (pintype "passive"))
      (node (ref "C95") (pin "2") (pinfunction "2_2") (pintype "passive"))
      (node (ref "D30") (pin "2") (pinfunction "A_2") (pintype "passive"))
      (node (ref "D31") (pin "2") (pinfunction "A_2") (pintype "passive"))
      (node (ref "D32") (pin "1") (pinfunction "K_1") (pintype "passive"))
      (node (ref "D33") (pin "1") (pinfunction "K_1") (pintype "passive"))
      (node (ref "E8") (pin "1") (pinfunction "NC_1") (pintype "passive"))
      (node (ref "R51") (pin "2") (pinfunction "2_2") (pintype "passive"))
      (node (ref "R52") (pin "2") (pinfunction "2_2") (pintype "passive"))
      (node (ref "R69") (pin "2") (pinfunction "2_2") (pintype "passive"))
      (node (ref "R71") (pin "1") (pinfunction "1_1") (pintype "passive"))
      (node (ref "U14") (pin "4") (pinfunction "REF_4") (pintype "power_in"))
      (node (ref "U15") (pin "4") (pinfunction "REF_4") (pintype "power_in"))
      (node (ref "U17") (pin "1") (pinfunction "GND1_1") (pintype "passive"))
      (node (ref "U17") (pin "3") (pinfunction "GND2_3") (pintype "passive"))
      (node (ref "U17") (pin "7") (pinfunction "SHDN_7") (pintype "passive"))
      (node (ref "U18") (pin "1") (pinfunction "Din-_1") (pintype "input"))
      (node (ref "U18") (pin "2") (pinfunction "Vcom_2") (pintype "passive"))
    )
    (net (code "18") (name "DGND") (class "Default")
      (node (ref "C12") (pin "1") (pinfunction "1_1") (pintype "passive"))
      (node (ref "C13") (pin "2") (pinfunction "2_2") (pintype "passive"))
      (node (ref "C14") (pin "1") (pinfunction "1_1") (pintype "passive"))
      (node (ref "C15") (pin "1") (pinfunction "1_1") (pintype "passive"))
      (node (ref "C16") (pin "2") (pinfunction "2_2") (pintype "passive"))
      (node (ref "C17") (pin "2") (pinfunction "2_2") (pintype "passive"))
      (node (ref "C18") (pin "2") (pinfunction "2_2") (pintype "passive"))
      (node (ref "C19") (pin "1") (pinfunction "1_1") (pintype "passive"))
      (node (ref "C22") (pin "2") (pinfunction "2_2") (pintype "passive"))
      (node (ref "C23") (pin "2") (pinfunction "2_2") (pintype "passive"))
      (node (ref "C24") (pin "2") (pinfunction "2_2") (pintype "passive"))
      (node (ref "C25") (pin "2") (pinfunction "2_2") (pintype "passive"))
      (node (ref "C26") (pin "1") (pinfunction "1_1") (pintype "passive"))
      (node (ref "C27") (pin "1") (pinfunction "1_1") (pintype "passive"))
      (node (ref "C28") (pin "1") (pinfunction "1_1") (pintype "passive"))
      (node (ref "C29") (pin "1") (pinfunction "1_1") (pintype "passive"))
      (node (ref "C3") (pin "2") (pinfunction "2_2") (pintype "passive"))
      (node (ref "C30") (pin "2") (pinfunction "2_2") (pintype "passive"))
      (node (ref "C31") (pin "2") (pinfunction "2_2") (pintype "passive"))
      (node (ref "C32") (pin "1") (pinfunction "1_1") (pintype "passive"))
      (node (ref "C33") (pin "1") (pinfunction "1_1") (pintype "passive"))
      (node (ref "C36") (pin "2") (pinfunction "2_2") (pintype "passive"))
      (node (ref "C4") (pin "2") (pinfunction "2_2") (pintype "passive"))
      (node (ref "C7") (pin "1") (pinfunction "1_1") (pintype "passive"))
      (node (ref "D12") (pin "1") (pinfunction "A_1") (pintype "passive"))
      (node (ref "D13") (pin "1") (pinfunction "A_1") (pintype "passive"))
      (node (ref "D5") (pin "2") (pintype "passive"))
      (node (ref "E11") (pin "1") (pinfunction "NC_1") (pintype "passive"))
      (node (ref "R11") (pin "1") (pinfunction "1_1") (pintype "passive"))
      (node (ref "R12") (pin "2") (pinfunction "2_2") (pintype "passive"))
      (node (ref "R15") (pin "1") (pinfunction "1_1") (pintype "passive"))
      (node (ref "R16") (pin "1") (pinfunction "1_1") (pintype "passive"))
      (node (ref "R18") (pin "2") (pinfunction "2_2") (pintype "passive"))
      (node (ref "R24") (pin "2") (pinfunction "2_2") (pintype "passive"))
      (node (ref "R33") (pin "1") (pinfunction "1_1") (pintype "passive"))
      (node (ref "R36") (pin "2") (pinfunction "2_2") (pintype "passive"))
      (node (ref "R7") (pin "1") (pinfunction "1_1") (pintype "passive"))
      (node (ref "R8") (pin "1") (pinfunction "1_1") (pintype "passive"))
      (node (ref "U1") (pin "12") (pinfunction "~{ENABLE}_12") (pintype "passive"))
      (node (ref "U1") (pin "8") (pinfunction "GND_8") (pintype "passive"))
      (node (ref "U2") (pin "4") (pinfunction "A_4") (pintype "input"))
      (node (ref "U2") (pin "5") (pinfunction "B_5") (pintype "input"))
      (node (ref "U2") (pin "7") (pinfunction "GND_7") (pintype "power_in"))
      (node (ref "U3") (pin "1") (pinfunction "A_1") (pintype "input"))
      (node (ref "U3") (pin "13") (pinfunction "A_13") (pintype "input"))
      (node (ref "U3") (pin "3") (pinfunction "A_3") (pintype "input"))
      (node (ref "U3") (pin "7") (pinfunction "GND_7") (pintype "power_in"))
      (node (ref "U4") (pin "4") (pinfunction "-Vs_4") (pintype "power_in"))
      (node (ref "U4") (pin "6") (pinfunction "GND_6") (pintype "power_in"))
      (node (ref "U5") (pin "4") (pinfunction "GND1_4") (pintype "passive"))
      (node (ref "U5") (pin "5") (pinfunction "GND2_5") (pintype "passive"))
      (node (ref "U6") (pin "4") (pinfunction "GND1_4") (pintype "passive"))
      (node (ref "U6") (pin "5") (pinfunction "GND2_5") (pintype "passive"))
      (node (ref "U7") (pin "4") (pinfunction "GND1_4") (pintype "passive"))
      (node (ref "U7") (pin "5") (pinfunction "GND2_5") (pintype "passive"))
      (node (ref "U8") (pin "4") (pinfunction "GND1_4") (pintype "passive"))
      (node (ref "U8") (pin "5") (pinfunction "GND2_5") (pintype "passive"))
      (node (ref "U9") (pin "4") (pinfunction "-Vs_4") (pintype "power_in"))
      (node (ref "U9") (pin "6") (pinfunction "GND_6") (pintype "power_in"))
    )
    (net (code "19") (name "Net-(C36-Pad1)") (class "Default")
      (node (ref "C36") (pin "1") (pinfunction "1_1") (pintype "passive"))
      (node (ref "R27") (pin "2") (pinfunction "2_2") (pintype "passive"))
      (node (ref "R30") (pin "1") (pinfunction "1_1") (pintype "passive"))
    )
    (net (code "20") (name "Net-(C39-Pad1)") (class "Default")
      (node (ref "C39") (pin "1") (pinfunction "1_1") (pintype "passive"))
      (node (ref "R37") (pin "1") (pinfunction "1_1") (pintype "passive"))
    )
    (net (code "21") (name "Net-(C40-Pad1)") (class "Default")
      (node (ref "C40") (pin "1") (pinfunction "1_1") (pintype "passive"))
      (node (ref "R38") (pin "1") (pinfunction "1_1") (pintype "passive"))
    )
    (net (code "22") (name "Net-(C51-Pad1)") (class "Default")
      (node (ref "C51") (pin "1") (pinfunction "1_1") (pintype "passive"))
      (node (ref "C54") (pin "1") (pinfunction "1_1") (pintype "passive"))
      (node (ref "R49") (pin "1") (pinfunction "1_1") (pintype "passive"))
      (node (ref "U12") (pin "7") (pinfunction "NC_7") (pintype "power_in"))
    )
    (net (code "23") (name "Net-(C55-Pad1)") (class "Default")
      (node (ref "C55") (pin "1") (pinfunction "1_1") (pintype "passive"))
      (node (ref "C56") (pin "1") (pinfunction "1_1") (pintype "passive"))
      (node (ref "R50") (pin "1") (pinfunction "1_1") (pintype "passive"))
      (node (ref "U13") (pin "7") (pinfunction "NC_7") (pintype "power_in"))
    )
    (net (code "24") (name "Net-(C57-Pad1)") (class "Default")
      (node (ref "C57") (pin "1") (pinfunction "1_1") (pintype "passive"))
      (node (ref "C58") (pin "1") (pinfunction "1_1") (pintype "passive"))
      (node (ref "R43") (pin "1") (pinfunction "1_1") (pintype "passive"))
      (node (ref "U10") (pin "7") (pinfunction "NC_7") (pintype "power_in"))
    )
    (net (code "25") (name "Net-(C59-Pad1)") (class "Default")
      (node (ref "C59") (pin "1") (pinfunction "1_1") (pintype "passive"))
      (node (ref "C60") (pin "1") (pinfunction "1_1") (pintype "passive"))
      (node (ref "R44") (pin "1") (pinfunction "1_1") (pintype "passive"))
      (node (ref "U11") (pin "7") (pinfunction "NC_7") (pintype "power_in"))
    )
    (net (code "26") (name "Net-(C73-Pad1)") (class "Default")
      (node (ref "C73") (pin "1") (pinfunction "1_1") (pintype "passive"))
      (node (ref "R55") (pin "1") (pinfunction "1_1") (pintype "passive"))
    )
    (net (code "27") (name "Net-(C74-Pad1)") (class "Default")
      (node (ref "C74") (pin "1") (pinfunction "1_1") (pintype "passive"))
      (node (ref "R56") (pin "1") (pinfunction "1_1") (pintype "passive"))
    )
    (net (code "28") (name "Net-(C82-Pad1)") (class "Default")
      (node (ref "C82") (pin "1") (pinfunction "1_1") (pintype "passive"))
      (node (ref "C84") (pin "1") (pinfunction "1_1") (pintype "passive"))
      (node (ref "R59") (pin "1") (pinfunction "1_1") (pintype "passive"))
      (node (ref "U16") (pin "7") (pinfunction "NC_7") (pintype "power_in"))
    )
    (net (code "29") (name "Net-(C85-Pad1)") (class "Default")
      (node (ref "C85") (pin "1") (pinfunction "1_1") (pintype "passive"))
      (node (ref "C97") (pin "1") (pinfunction "1_1") (pintype "passive"))
      (node (ref "R72") (pin "1") (pinfunction "1_1") (pintype "passive"))
    )
    (net (code "30") (name "Net-(C93-Pad1)") (class "Default")
      (node (ref "C93") (pin "1") (pinfunction "1_1") (pintype "passive"))
      (node (ref "C95") (pin "1") (pinfunction "1_1") (pintype "passive"))
      (node (ref "R65") (pin "1") (pinfunction "1_1") (pintype "passive"))
      (node (ref "U19") (pin "7") (pinfunction "NC_7") (pintype "power_in"))
    )
    (net (code "31") (name "Net-(D1-A)") (class "Default")
      (node (ref "D1") (pin "1") (pinfunction "A_1") (pintype "passive"))
      (node (ref "R5") (pin "2") (pinfunction "2_2") (pintype "passive"))
      (node (ref "R7") (pin "2") (pinfunction "2_2") (pintype "passive"))
    )
    (net (code "32") (name "Net-(D1-K)") (class "Default")
      (node (ref "C12") (pin "2") (pinfunction "2_2") (pintype "passive"))
      (node (ref "D1") (pin "2") (pinfunction "K_2") (pintype "passive"))
      (node (ref "D2") (pin "2") (pinfunction "K_2") (pintype "passive"))
      (node (ref "D3") (pin "3") (pinfunction "A_3") (pintype "passive"))
      (node (ref "R11") (pin "2") (pinfunction "2_2") (pintype "passive"))
      (node (ref "U4") (pin "2") (pinfunction "IN+_2") (pintype "input"))
    )
    (net (code "33") (name "Net-(D2-A)") (class "Default")
      (node (ref "D2") (pin "1") (pinfunction "A_1") (pintype "passive"))
      (node (ref "R6") (pin "2") (pinfunction "2_2") (pintype "passive"))
      (node (ref "R8") (pin "2") (pinfunction "2_2") (pintype "passive"))
    )
    (net (code "34") (name "Net-(D4-A)") (class "Default")
      (node (ref "D3") (pin "2") (pintype "passive"))
      (node (ref "D4") (pin "3") (pinfunction "A_3") (pintype "passive"))
    )
    (net (code "35") (name "Net-(D5-A)") (class "Default")
      (node (ref "D4") (pin "2") (pintype "passive"))
      (node (ref "D5") (pin "3") (pinfunction "A_3") (pintype "passive"))
    )
    (net (code "36") (name "Net-(D6-K)") (class "Default")
      (node (ref "D6") (pin "2") (pinfunction "K_2") (pintype "passive"))
      (node (ref "D7") (pin "3") (pinfunction "A_3") (pintype "passive"))
    )
    (net (code "37") (name "Net-(D7-K)") (class "Default")
      (node (ref "D7") (pin "2") (pinfunction "K_2") (pintype "passive"))
      (node (ref "D8") (pin "3") (pinfunction "A_3") (pintype "passive"))
    )
    (net (code "38") (name "Net-(D10-A)") (class "Default")
      (node (ref "D10") (pin "3") (pinfunction "A_3") (pintype "passive"))
      (node (ref "D11") (pin "2") (pinfunction "K_2") (pintype "passive"))
    )
    (net (code "39") (name "Net-(D10-K)") (class "Default")
      (node (ref "D10") (pin "2") (pinfunction "K_2") (pintype "passive"))
      (node (ref "D9") (pin "3") (pinfunction "A_3") (pintype "passive"))
    )
    (net (code "40") (name "Net-(D12-K)") (class "Default")
      (node (ref "C21") (pin "2") (pinfunction "2_2") (pintype "passive"))
      (node (ref "D12") (pin "2") (pinfunction "K_2") (pintype "passive"))
      (node (ref "R15") (pin "2") (pinfunction "2_2") (pintype "passive"))
      (node (ref "TP5") (pin "1") (pinfunction "NC_1") (pintype "passive"))
      (node (ref "U6") (pin "2") (pinfunction "IN_2") (pintype "passive"))
      (node (ref "U8") (pin "2") (pinfunction "IN_2") (pintype "passive"))
    )
    (net (code "41") (name "Net-(D13-K)") (class "Default")
      (node (ref "C20") (pin "2") (pinfunction "2_2") (pintype "passive"))
      (node (ref "D13") (pin "2") (pinfunction "K_2") (pintype "passive"))
      (node (ref "R16") (pin "2") (pinfunction "2_2") (pintype "passive"))
      (node (ref "TP4") (pin "1") (pinfunction "NC_1") (pintype "passive"))
      (node (ref "U5") (pin "2") (pinfunction "IN_2") (pintype "passive"))
      (node (ref "U7") (pin "2") (pinfunction "IN_2") (pintype "passive"))
    )
    (net (code "42") (name "Net-(D14-A)") (class "Default")
      (node (ref "D14") (pin "3") (pinfunction "A_3") (pintype "passive"))
      (node (ref "R19") (pin "1") (pinfunction "1_1") (pintype "passive"))
      (node (ref "U5") (pin "6") (pinfunction "OUT1_6") (pintype "passive"))
      (node (ref "U5") (pin "7") (pinfunction "OUT2_7") (pintype "passive"))
    )
    (net (code "43") (name "Net-(D15-A)") (class "Default")
      (node (ref "D15") (pin "3") (pinfunction "A_3") (pintype "passive"))
      (node (ref "R20") (pin "1") (pinfunction "1_1") (pintype "passive"))
      (node (ref "U6") (pin "6") (pinfunction "OUT1_6") (pintype "passive"))
      (node (ref "U6") (pin "7") (pinfunction "OUT2_7") (pintype "passive"))
    )
    (net (code "44") (name "Net-(D16-A)") (class "Default")
      (node (ref "D16") (pin "3") (pinfunction "A_3") (pintype "passive"))
      (node (ref "R21") (pin "1") (pinfunction "1_1") (pintype "passive"))
      (node (ref "U7") (pin "6") (pinfunction "OUT1_6") (pintype "passive"))
      (node (ref "U7") (pin "7") (pinfunction "OUT2_7") (pintype "passive"))
    )
    (net (code "45") (name "Net-(D17-A)") (class "Default")
      (node (ref "D17") (pin "3") (pinfunction "A_3") (pintype "passive"))
      (node (ref "R22") (pin "1") (pinfunction "1_1") (pintype "passive"))
      (node (ref "U8") (pin "6") (pinfunction "OUT1_6") (pintype "passive"))
      (node (ref "U8") (pin "7") (pinfunction "OUT2_7") (pintype "passive"))
    )
    (net (code "46") (name "Net-(D18-A)") (class "Default")
      (node (ref "D18") (pin "1") (pinfunction "A_1") (pintype "passive"))
      (node (ref "D30") (pin "1") (pinfunction "K_1") (pintype "passive"))
      (node (ref "D32") (pin "2") (pinfunction "A_2") (pintype "passive"))
      (node (ref "R31") (pin "2") (pinfunction "2_2") (pintype "passive"))
      (node (ref "R35") (pin "1") (pinfunction "1_1") (pintype "passive"))
      (node (ref "TP11") (pin "1") (pinfunction "NC_1") (pintype "passive"))
      (node (ref "U10") (pin "3") (pinfunction "+IN_3") (pintype "input"))
      (node (ref "U11") (pin "3") (pinfunction "+IN_3") (pintype "input"))
    )
    (net (code "47") (name "Net-(D18-K)") (class "Default")
      (node (ref "C33") (pin "2") (pinfunction "2_2") (pintype "passive"))
      (node (ref "D18") (pin "2") (pinfunction "K_2") (pintype "passive"))
      (node (ref "D19") (pin "2") (pinfunction "K_2") (pintype "passive"))
      (node (ref "R24") (pin "1") (pinfunction "1_1") (pintype "passive"))
      (node (ref "U9") (pin "2") (pinfunction "IN+_2") (pintype "input"))
    )
    (net (code "48") (name "Net-(D19-A)") (class "Default")
      (node (ref "D19") (pin "1") (pinfunction "A_1") (pintype "passive"))
      (node (ref "D31") (pin "1") (pinfunction "K_1") (pintype "passive"))
      (node (ref "D33") (pin "2") (pinfunction "A_2") (pintype "passive"))
      (node (ref "R32") (pin "1") (pinfunction "1_1") (pintype "passive"))
      (node (ref "R34") (pin "2") (pinfunction "2_2") (pintype "passive"))
      (node (ref "TP10") (pin "1") (pinfunction "NC_1") (pintype "passive"))
      (node (ref "U12") (pin "3") (pinfunction "+IN_3") (pintype "input"))
      (node (ref "U13") (pin "3") (pinfunction "+IN_3") (pintype "input"))
    )
    (net (code "49") (name "Net-(D20-A)") (class "Default")
      (node (ref "D20") (pin "2") (pinfunction "A_2") (pintype "passive"))
      (node (ref "T2") (pin "4") (pinfunction "Sec1+_4") (pintype "passive"))
    )
    (net (code "50") (name "Net-(D20-K)") (class "Default")
      (node (ref "D20") (pin "1") (pinfunction "K_1") (pintype "passive"))
      (node (ref "D26") (pin "1") (pinfunction "K_1") (pintype "passive"))
      (node (ref "Q4") (pin "1") (pinfunction "G_1") (pintype "passive"))
      (node (ref "Q7") (pin "1") (pinfunction "G_1") (pintype "passive"))
      (node (ref "R28") (pin "1") (pinfunction "1_1") (pintype "passive"))
    )
    (net (code "51") (name "Net-(D21-A)") (class "Default")
      (node (ref "C35") (pin "1") (pinfunction "1_1") (pintype "passive"))
      (node (ref "D21") (pin "2") (pinfunction "A_2") (pintype "passive"))
      (node (ref "D27") (pin "1") (pinfunction "A_1") (pintype "passive"))
      (node (ref "Q1") (pin "2") (pinfunction "S_2") (pintype "passive"))
      (node (ref "Q5") (pin "3") (pinfunction "G_3") (pintype "passive"))
      (node (ref "R25") (pin "2") (pinfunction "2_2") (pintype "passive"))
      (node (ref "T1") (pin "1") (pinfunction "Sec+_1") (pintype "passive"))
    )
    (net (code "52") (name "Net-(D21-K)") (class "Default")
      (node (ref "D21") (pin "1") (pinfunction "K_1") (pintype "passive"))
      (node (ref "T2") (pin "3") (pinfunction "Sec2-_3") (pintype "passive"))
    )
    (net (code "53") (name "Net-(D22-A)") (class "Default")
      (node (ref "D22") (pin "2") (pinfunction "A_2") (pintype "passive"))
      (node (ref "T1") (pin "2") (pinfunction "Sec-_2") (pintype "passive"))
    )
    (net (code "54") (name "Net-(D22-K)") (class "Default")
      (node (ref "D22") (pin "1") (pinfunction "K_1") (pintype "passive"))
      (node (ref "D27") (pin "2") (pinfunction "K_2") (pintype "passive"))
      (node (ref "Q1") (pin "1") (pinfunction "G_1") (pintype "passive"))
      (node (ref "R25") (pin "1") (pinfunction "1_1") (pintype "passive"))
    )
    (net (code "55") (name "Net-(D23-A)") (class "Default")
      (node (ref "D23") (pin "2") (pinfunction "A_2") (pintype "passive"))
      (node (ref "T4") (pin "4") (pinfunction "Sec1+_4") (pintype "passive"))
    )
    (net (code "56") (name "Net-(D23-K)") (class "Default")
      (node (ref "D23") (pin "1") (pinfunction "K_1") (pintype "passive"))
      (node (ref "D28") (pin "1") (pinfunction "K_1") (pintype "passive"))
      (node (ref "Q3") (pin "1") (pinfunction "G_1") (pintype "passive"))
      (node (ref "Q8") (pin "1") (pinfunction "G_1") (pintype "passive"))
      (node (ref "R29") (pin "1") (pinfunction "1_1") (pintype "passive"))
    )
    (net (code "57") (name "Net-(D24-A)") (class "Default")
      (node (ref "C34") (pin "1") (pinfunction "1_1") (pintype "passive"))
      (node (ref "D24") (pin "2") (pinfunction "A_2") (pintype "passive"))
      (node (ref "D29") (pin "1") (pinfunction "A_1") (pintype "passive"))
      (node (ref "Q2") (pin "2") (pinfunction "S_2") (pintype "passive"))
      (node (ref "Q6") (pin "3") (pinfunction "G_3") (pintype "passive"))
      (node (ref "R26") (pin "2") (pinfunction "2_2") (pintype "passive"))
      (node (ref "T3") (pin "1") (pinfunction "Sec+_1") (pintype "passive"))
    )
    (net (code "58") (name "Net-(D24-K)") (class "Default")
      (node (ref "D24") (pin "1") (pinfunction "K_1") (pintype "passive"))
      (node (ref "T4") (pin "3") (pinfunction "Sec2-_3") (pintype "passive"))
    )
    (net (code "59") (name "Net-(D25-A)") (class "Default")
      (node (ref "D25") (pin "2") (pinfunction "A_2") (pintype "passive"))
      (node (ref "T3") (pin "2") (pinfunction "Sec-_2") (pintype "passive"))
    )
    (net (code "60") (name "Net-(D25-K)") (class "Default")
      (node (ref "D25") (pin "1") (pinfunction "K_1") (pintype "passive"))
      (node (ref "D29") (pin "2") (pinfunction "K_2") (pintype "passive"))
      (node (ref "Q2") (pin "1") (pinfunction "G_1") (pintype "passive"))
      (node (ref "R26") (pin "1") (pinfunction "1_1") (pintype "passive"))
    )
    (net (code "61") (name "Net-(D26-A)") (class "Default")
      (node (ref "C35") (pin "2") (pinfunction "2_2") (pintype "passive"))
      (node (ref "C37") (pin "1") (pinfunction "1_1") (pintype "passive"))
      (node (ref "D26") (pin "2") (pinfunction "A_2") (pintype "passive"))
      (node (ref "Q1") (pin "3") (pinfunction "D_3") (pintype "passive"))
      (node (ref "Q4") (pin "3") (pinfunction "S_3") (pintype "passive"))
      (node (ref "Q5") (pin "1") (pinfunction "D_1") (pintype "passive"))
      (node (ref "Q7") (pin "3") (pinfunction "S_3") (pintype "passive"))
      (node (ref "T2") (pin "2") (pinfunction "Sec2+_2") (pintype "passive"))
      (node (ref "T2") (pin "5") (pinfunction "Sec1-_5") (pintype "passive"))
      (node (ref "TP7") (pin "1") (pinfunction "NC_1") (pintype "passive"))
    )
    (net (code "62") (name "Net-(D28-A)") (class "Default")
      (node (ref "C34") (pin "2") (pinfunction "2_2") (pintype "passive"))
      (node (ref "C38") (pin "1") (pinfunction "1_1") (pintype "passive"))
      (node (ref "D28") (pin "2") (pinfunction "A_2") (pintype "passive"))
      (node (ref "Q2") (pin "3") (pinfunction "D_3") (pintype "passive"))
      (node (ref "Q3") (pin "3") (pinfunction "S_3") (pintype "passive"))
      (node (ref "Q6") (pin "1") (pinfunction "D_1") (pintype "passive"))
      (node (ref "Q8") (pin "3") (pinfunction "S_3") (pintype "passive"))
      (node (ref "T4") (pin "2") (pinfunction "Sec2+_2") (pintype "passive"))
      (node (ref "T4") (pin "5") (pinfunction "Sec1-_5") (pintype "passive"))
      (node (ref "TP8") (pin "1") (pinfunction "NC_1") (pintype "passive"))
    )
    (net (code "63") (name "Net-(D34-A)") (class "Default")
      (node (ref "D34") (pin "3") (pinfunction "A_3") (pintype "passive"))
      (node (ref "D36") (pin "2") (pinfunction "K_2") (pintype "passive"))
    )
    (net (code "64") (name "Net-(D34-K)") (class "Default")
      (node (ref "C88") (pin "1") (pinfunction "1_1") (pintype "passive"))
      (node (ref "C89") (pin "1") (pinfunction "1_1") (pintype "passive"))
      (node (ref "D34") (pin "2") (pinfunction "K_2") (pintype "passive"))
      (node (ref "U18") (pin "3") (pinfunction "V+_3") (pintype "power_in"))
    )
    (net (code "65") (name "Net-(D35-A)") (class "Default")
      (node (ref "C90") (pin "2") (pinfunction "2_2") (pintype "passive"))
      (node (ref "C91") (pin "2") (pinfunction "2_2") (pintype "passive"))
      (node (ref "D35") (pin "3") (pinfunction "A_3") (pintype "passive"))
      (node (ref "U18") (pin "6") (pinfunction "V-_6") (pintype "power_in"))
    )
    (net (code "66") (name "Net-(D35-K)") (class "Default")
      (node (ref "D35") (pin "2") (pinfunction "K_2") (pintype "passive"))
      (node (ref "D37") (pin "3") (pinfunction "A_3") (pintype "passive"))
    )
    (net (code "67") (name "Net-(Q5-S)") (class "Default")
      (node (ref "C37") (pin "2") (pinfunction "2_2") (pintype "passive"))
      (node (ref "Q5") (pin "2") (pinfunction "S_2") (pintype "passive"))
      (node (ref "R28") (pin "2") (pinfunction "2_2") (pintype "passive"))
    )
    (net (code "68") (name "Net-(Q6-S)") (class "Default")
      (node (ref "C38") (pin "2") (pinfunction "2_2") (pintype "passive"))
      (node (ref "Q6") (pin "2") (pinfunction "S_2") (pintype "passive"))
      (node (ref "R29") (pin "2") (pinfunction "2_2") (pintype "passive"))
    )
    (net (code "69") (name "Net-(Q7-D)") (class "Default")
      (node (ref "Q7") (pin "2") (pinfunction "D_2") (pintype "passive"))
      (node (ref "R31") (pin "1") (pinfunction "1_1") (pintype "passive"))
    )
    (net (code "70") (name "Net-(Q8-D)") (class "Default")
      (node (ref "Q8") (pin "2") (pinfunction "D_2") (pintype "passive"))
      (node (ref "R32") (pin "2") (pinfunction "2_2") (pintype "passive"))
    )
    (net (code "71") (name "Net-(Q9A-D-Pad5)") (class "Default")
      (node (ref "Q9") (pin "5") (pinfunction "D_5") (pintype "passive"))
      (node (ref "Q9") (pin "6") (pinfunction "D_6") (pintype "passive"))
      (node (ref "R34") (pin "1") (pinfunction "1_1") (pintype "passive"))
    )
    (net (code "72") (name "Net-(Q9A-G)") (class "Default")
      (node (ref "Q9") (pin "2") (pinfunction "G_2") (pintype "passive"))
      (node (ref "Q9") (pin "4") (pinfunction "G_4") (pintype "passive"))
      (node (ref "R30") (pin "2") (pinfunction "2_2") (pintype "passive"))
      (node (ref "R33") (pin "2") (pinfunction "2_2") (pintype "passive"))
      (node (ref "TP9") (pin "1") (pinfunction "NC_1") (pintype "passive"))
    )
    (net (code "73") (name "Net-(Q9A-S)") (class "Default")
      (node (ref "Q9") (pin "1") (pinfunction "S_1") (pintype "passive"))
      (node (ref "Q9") (pin "3") (pinfunction "S_3") (pintype "passive"))
      (node (ref "R36") (pin "1") (pinfunction "1_1") (pintype "passive"))
    )
    (net (code "74") (name "Net-(Q9B-D-Pad7)") (class "Default")
      (node (ref "Q9") (pin "7") (pinfunction "D_7") (pintype "passive"))
      (node (ref "Q9") (pin "8") (pinfunction "D_8") (pintype "passive"))
      (node (ref "R35") (pin "2") (pinfunction "2_2") (pintype "passive"))
    )
    (net (code "75") (name "Net-(R20-Pad2)") (class "Default")
      (node (ref "R20") (pin "2") (pinfunction "2_2") (pintype "passive"))
      (node (ref "T1") (pin "3") (pinfunction "Pri-_3") (pintype "passive"))
    )
    (net (code "76") (name "Net-(R22-Pad2)") (class "Default")
      (node (ref "R22") (pin "2") (pinfunction "2_2") (pintype "passive"))
      (node (ref "T3") (pin "3") (pinfunction "Pri-_3") (pintype "passive"))
    )
    (net (code "77") (name "Net-(R55-Pad2)") (class "Default")
      (node (ref "R55") (pin "2") (pinfunction "2_2") (pintype "passive"))
      (node (ref "R56") (pin "2") (pinfunction "2_2") (pintype "passive"))
      (node (ref "R67") (pin "1") (pinfunction "1_1") (pintype "passive"))
    )
    (net (code "78") (name "Net-(T2-Pri-)") (class "Default")
      (node (ref "R19") (pin "2") (pinfunction "2_2") (pintype "passive"))
      (node (ref "T2") (pin "1") (pinfunction "Pri-_1") (pintype "passive"))
    )
    (net (code "79") (name "Net-(T4-Pri-)") (class "Default")
      (node (ref "R21") (pin "2") (pinfunction "2_2") (pintype "passive"))
      (node (ref "T4") (pin "1") (pinfunction "Pri-_1") (pintype "passive"))
    )
    (net (code "80") (name "Net-(TP1-NC)") (class "Default")
      (node (ref "TP1") (pin "1") (pinfunction "NC_1") (pintype "passive"))
      (node (ref "U1") (pin "3") (pinfunction "OUTA_3") (pintype "passive"))
      (node (ref "U2") (pin "9") (pinfunction "B_9") (pintype "input"))
    )
    (net (code "81") (name "Net-(TP2-NC)") (class "Default")
      (node (ref "R27") (pin "1") (pinfunction "1_1") (pintype "passive"))
      (node (ref "TP2") (pin "1") (pinfunction "NC_1") (pintype "passive"))
      (node (ref "U1") (pin "5") (pinfunction "OUTC_5") (pintype "passive"))
    )
    (net (code "82") (name "Net-(TP12-NC)") (class "Default")
      (node (ref "C52") (pin "1") (pinfunction "1_1") (pintype "passive"))
      (node (ref "C63") (pin "1") (pinfunction "1_1") (pintype "passive"))
      (node (ref "R41") (pin "1") (pinfunction "1_1") (pintype "passive"))
      (node (ref "TP12") (pin "1") (pinfunction "NC_1") (pintype "passive"))
      (node (ref "U10") (pin "6") (pinfunction "OUTPUT_6") (pintype "output"))
      (node (ref "U14") (pin "1") (pinfunction "+IN_1") (pintype "input"))
    )
    (net (code "83") (name "Net-(TP13-NC)") (class "Default")
      (node (ref "C53") (pin "1") (pinfunction "1_1") (pintype "passive"))
      (node (ref "C64") (pin "1") (pinfunction "1_1") (pintype "passive"))
      (node (ref "R42") (pin "1") (pinfunction "1_1") (pintype "passive"))
      (node (ref "TP13") (pin "1") (pinfunction "NC_1") (pintype "passive"))
      (node (ref "U11") (pin "6") (pinfunction "OUTPUT_6") (pintype "output"))
      (node (ref "U15") (pin "1") (pinfunction "+IN_1") (pintype "input"))
    )
    (net (code "84") (name "Net-(TP14-NC)") (class "Default")
      (node (ref "C50") (pin "2") (pinfunction "2_2") (pintype "passive"))
      (node (ref "C62") (pin "1") (pinfunction "1_1") (pintype "passive"))
      (node (ref "R40") (pin "2") (pinfunction "2_2") (pintype "passive"))
      (node (ref "TP14") (pin "1") (pinfunction "NC_1") (pintype "passive"))
      (node (ref "U13") (pin "6") (pinfunction "OUTPUT_6") (pintype "output"))
      (node (ref "U15") (pin "8") (pinfunction "-IN_8") (pintype "input"))
    )
    (net (code "85") (name "Net-(TP15-NC)") (class "Default")
      (node (ref "C49") (pin "2") (pinfunction "2_2") (pintype "passive"))
      (node (ref "C61") (pin "1") (pinfunction "1_1") (pintype "passive"))
      (node (ref "R39") (pin "2") (pinfunction "2_2") (pintype "passive"))
      (node (ref "TP15") (pin "1") (pinfunction "NC_1") (pintype "passive"))
      (node (ref "U12") (pin "6") (pinfunction "OUTPUT_6") (pintype "output"))
      (node (ref "U14") (pin "8") (pinfunction "-IN_8") (pintype "input"))
    )
    (net (code "86") (name "Net-(TP16-NC)") (class "Default")
      (node (ref "C73") (pin "2") (pinfunction "2_2") (pintype "passive"))
      (node (ref "R53") (pin "2") (pinfunction "2_2") (pintype "passive"))
      (node (ref "TP16") (pin "1") (pinfunction "NC_1") (pintype "passive"))
      (node (ref "U14") (pin "6") (pinfunction "OUTPUT_6") (pintype "output"))
    )
    (net (code "87") (name "Net-(TP18-NC)") (class "Default")
      (node (ref "TP18") (pin "1") (pinfunction "NC_1") (pintype "passive"))
      (node (ref "U17") (pin "8") (pinfunction "VO_8") (pintype "passive"))
      (node (ref "U18") (pin "8") (pinfunction "Din+_8") (pintype "input"))
    )
    (net (code "88") (name "Net-(TP19-NC)") (class "Default")
      (node (ref "C81") (pin "1") (pinfunction "1_1") (pintype "passive"))
      (node (ref "C83") (pin "1") (pinfunction "1_1") (pintype "passive"))
      (node (ref "C85") (pin "2") (pinfunction "2_2") (pintype "passive"))
      (node (ref "R58") (pin "2") (pinfunction "2_2") (pintype "passive"))
      (node (ref "TP19") (pin "1") (pinfunction "NC_1") (pintype "passive"))
      (node (ref "U16") (pin "6") (pinfunction "OUTPUT_6") (pintype "output"))
    )
    (net (code "89") (name "Net-(TP23-NC)") (class "Default")
      (node (ref "C74") (pin "2") (pinfunction "2_2") (pintype "passive"))
      (node (ref "R54") (pin "2") (pinfunction "2_2") (pintype "passive"))
      (node (ref "TP23") (pin "1") (pinfunction "NC_1") (pintype "passive"))
      (node (ref "U15") (pin "6") (pinfunction "OUTPUT_6") (pintype "output"))
    )
    (net (code "90") (name "Net-(U1-INA+)") (class "Default")
      (node (ref "R1") (pin "2") (pinfunction "2_2") (pintype "passive"))
      (node (ref "U1") (pin "2") (pinfunction "INA+_2") (pintype "passive"))
    )
    (net (code "91") (name "Net-(U1-INA-)") (class "Default")
      (node (ref "R2") (pin "2") (pinfunction "2_2") (pintype "passive"))
      (node (ref "U1") (pin "1") (pinfunction "INA-_1") (pintype "passive"))
    )
    (net (code "92") (name "Net-(U1-INC+)") (class "Default")
      (node (ref "R3") (pin "2") (pinfunction "2_2") (pintype "passive"))
      (node (ref "U1") (pin "6") (pinfunction "INC+_6") (pintype "passive"))
    )
    (net (code "93") (name "Net-(U1-INC-)") (class "Default")
      (node (ref "R4") (pin "2") (pinfunction "2_2") (pintype "passive"))
      (node (ref "U1") (pin "7") (pinfunction "INC-_7") (pintype "passive"))
    )
    (net (code "94") (name "Net-(U2A-A)") (class "Default")
      (node (ref "C16") (pin "1") (pinfunction "1_1") (pintype "passive"))
      (node (ref "R14") (pin "2") (pinfunction "2_2") (pintype "passive"))
      (node (ref "U2") (pin "1") (pinfunction "A_1") (pintype "input"))
    )
    (net (code "95") (name "Net-(U2A-~{O})") (class "Default")
      (node (ref "U2") (pin "13") (pinfunction "A_13") (pintype "input"))
      (node (ref "U2") (pin "3") (pinfunction "~{O}_3") (pintype "output"))
    )
    (net (code "96") (name "Net-(U2C-B)") (class "Default")
      (node (ref "U2") (pin "12") (pinfunction "B_12") (pintype "input"))
      (node (ref "U3") (pin "10") (pinfunction "~{O}_10") (pintype "output"))
    )
    (net (code "97") (name "Net-(U2C-~{O})") (class "Default")
      (node (ref "C21") (pin "1") (pinfunction "1_1") (pintype "passive"))
      (node (ref "U2") (pin "11") (pinfunction "~{O}_11") (pintype "output"))
    )
    (net (code "98") (name "Net-(U2D-~{O})") (class "Default")
      (node (ref "R9") (pin "2") (pinfunction "2_2") (pintype "passive"))
      (node (ref "U2") (pin "8") (pinfunction "~{O}_8") (pintype "output"))
      (node (ref "U3") (pin "11") (pinfunction "A_11") (pintype "input"))
    )
    (net (code "99") (name "Net-(U3C-A)") (class "Default")
      (node (ref "U3") (pin "5") (pinfunction "A_5") (pintype "input"))
      (node (ref "U4") (pin "7") (pinfunction "OUT_7") (pintype "output"))
    )
    (net (code "100") (name "Net-(U3F-A)") (class "Default")
      (node (ref "C13") (pin "1") (pinfunction "1_1") (pintype "passive"))
      (node (ref "R9") (pin "1") (pinfunction "1_1") (pintype "passive"))
      (node (ref "U3") (pin "9") (pinfunction "A_9") (pintype "input"))
    )
    (net (code "101") (name "Net-(U3F-~{O})") (class "Default")
      (node (ref "C20") (pin "1") (pinfunction "1_1") (pintype "passive"))
      (node (ref "R14") (pin "1") (pinfunction "1_1") (pintype "passive"))
      (node (ref "U3") (pin "8") (pinfunction "~{O}_8") (pintype "output"))
    )
    (net (code "102") (name "Net-(U4-IN-)") (class "Default")
      (node (ref "C15") (pin "2") (pinfunction "2_2") (pintype "passive"))
      (node (ref "R10") (pin "1") (pinfunction "1_1") (pintype "passive"))
      (node (ref "R12") (pin "1") (pinfunction "1_1") (pintype "passive"))
      (node (ref "U4") (pin "3") (pinfunction "IN-_3") (pintype "input"))
    )
    (net (code "103") (name "Net-(U4-~{latch})") (class "Default")
      (node (ref "R13") (pin "1") (pinfunction "1_1") (pintype "passive"))
      (node (ref "U4") (pin "5") (pinfunction "~{latch}_5") (pintype "passive"))
    )
    (net (code "104") (name "Net-(U9-IN-)") (class "Default")
      (node (ref "C32") (pin "2") (pinfunction "2_2") (pintype "passive"))
      (node (ref "R18") (pin "1") (pinfunction "1_1") (pintype "passive"))
      (node (ref "R23") (pin "1") (pinfunction "1_1") (pintype "passive"))
      (node (ref "U9") (pin "3") (pinfunction "IN-_3") (pintype "input"))
    )
    (net (code "105") (name "Net-(U9-~{latch})") (class "Default")
      (node (ref "R17") (pin "1") (pinfunction "1_1") (pintype "passive"))
      (node (ref "U9") (pin "5") (pinfunction "~{latch}_5") (pintype "passive"))
    )
    (net (code "106") (name "Net-(U10--IN)") (class "Default")
      (node (ref "C39") (pin "2") (pinfunction "2_2") (pintype "passive"))
      (node (ref "C52") (pin "2") (pinfunction "2_2") (pintype "passive"))
      (node (ref "R41") (pin "2") (pinfunction "2_2") (pintype "passive"))
      (node (ref "U10") (pin "2") (pinfunction "-IN_2") (pintype "input"))
    )
    (net (code "107") (name "Net-(U10--VS)") (class "Default")
      (node (ref "C46") (pin "2") (pinfunction "2_2") (pintype "passive"))
      (node (ref "C47") (pin "2") (pinfunction "2_2") (pintype "passive"))
      (node (ref "R45") (pin "1") (pinfunction "1_1") (pintype "passive"))
      (node (ref "U10") (pin "4") (pinfunction "-VS_4") (pintype "power_in"))
    )
    (net (code "108") (name "Net-(U10-NEU)") (class "Default")
      (node (ref "C63") (pin "2") (pinfunction "2_2") (pintype "passive"))
      (node (ref "U10") (pin "8") (pinfunction "NEU_8") (pintype "power_in"))
    )
    (net (code "109") (name "Net-(U11--IN)") (class "Default")
      (node (ref "C40") (pin "2") (pinfunction "2_2") (pintype "passive"))
      (node (ref "C53") (pin "2") (pinfunction "2_2") (pintype "passive"))
      (node (ref "R42") (pin "2") (pinfunction "2_2") (pintype "passive"))
      (node (ref "U11") (pin "2") (pinfunction "-IN_2") (pintype "input"))
    )
    (net (code "110") (name "Net-(U11--VS)") (class "Default")
      (node (ref "C43") (pin "2") (pinfunction "2_2") (pintype "passive"))
      (node (ref "C48") (pin "2") (pinfunction "2_2") (pintype "passive"))
      (node (ref "R47") (pin "1") (pinfunction "1_1") (pintype "passive"))
      (node (ref "U11") (pin "4") (pinfunction "-VS_4") (pintype "power_in"))
    )
    (net (code "111") (name "Net-(U11-NEU)") (class "Default")
      (node (ref "C64") (pin "2") (pinfunction "2_2") (pintype "passive"))
      (node (ref "U11") (pin "8") (pinfunction "NEU_8") (pintype "power_in"))
    )
    (net (code "112") (name "Net-(U12--IN)") (class "Default")
      (node (ref "C49") (pin "1") (pinfunction "1_1") (pintype "passive"))
      (node (ref "R37") (pin "2") (pinfunction "2_2") (pintype "passive"))
      (node (ref "R39") (pin "1") (pinfunction "1_1") (pintype "passive"))
      (node (ref "U12") (pin "2") (pinfunction "-IN_2") (pintype "input"))
    )
    (net (code "113") (name "Net-(U12--VS)") (class "Default")
      (node (ref "C41") (pin "2") (pinfunction "2_2") (pintype "passive"))
      (node (ref "C42") (pin "2") (pinfunction "2_2") (pintype "passive"))
      (node (ref "R46") (pin "1") (pinfunction "1_1") (pintype "passive"))
      (node (ref "U12") (pin "4") (pinfunction "-VS_4") (pintype "power_in"))
    )
    (net (code "114") (name "Net-(U12-NEU)") (class "Default")
      (node (ref "C61") (pin "2") (pinfunction "2_2") (pintype "passive"))
      (node (ref "U12") (pin "8") (pinfunction "NEU_8") (pintype "power_in"))
    )
    (net (code "115") (name "Net-(U13--IN)") (class "Default")
      (node (ref "C50") (pin "1") (pinfunction "1_1") (pintype "passive"))
      (node (ref "R38") (pin "2") (pinfunction "2_2") (pintype "passive"))
      (node (ref "R40") (pin "1") (pinfunction "1_1") (pintype "passive"))
      (node (ref "U13") (pin "2") (pinfunction "-IN_2") (pintype "input"))
    )
    (net (code "116") (name "Net-(U13--VS)") (class "Default")
      (node (ref "C44") (pin "2") (pinfunction "2_2") (pintype "passive"))
      (node (ref "C45") (pin "1") (pinfunction "1_1") (pintype "passive"))
      (node (ref "R48") (pin "1") (pinfunction "1_1") (pintype "passive"))
      (node (ref "U13") (pin "4") (pinfunction "-VS_4") (pintype "power_in"))
    )
    (net (code "117") (name "Net-(U13-NEU)") (class "Default")
      (node (ref "C62") (pin "2") (pinfunction "2_2") (pintype "passive"))
      (node (ref "U13") (pin "8") (pinfunction "NEU_8") (pintype "power_in"))
    )
    (net (code "118") (name "Net-(U14-FB)") (class "Default")
      (node (ref "R51") (pin "1") (pinfunction "1_1") (pintype "passive"))
      (node (ref "R53") (pin "1") (pinfunction "1_1") (pintype "passive"))
      (node (ref "U14") (pin "5") (pinfunction "FB_5") (pintype "power_in"))
    )
    (net (code "119") (name "Net-(U15-FB)") (class "Default")
      (node (ref "R52") (pin "1") (pinfunction "1_1") (pintype "passive"))
      (node (ref "R54") (pin "1") (pinfunction "1_1") (pintype "passive"))
      (node (ref "U15") (pin "5") (pinfunction "FB_5") (pintype "power_in"))
    )
    (net (code "120") (name "Net-(U16-+IN)") (class "Default")
      (node (ref "R69") (pin "1") (pinfunction "1_1") (pintype "passive"))
      (node (ref "U16") (pin "3") (pinfunction "+IN_3") (pintype "input"))
    )
    (net (code "121") (name "Net-(U16--IN)") (class "Default")
      (node (ref "C81") (pin "2") (pinfunction "2_2") (pintype "passive"))
      (node (ref "R58") (pin "1") (pinfunction "1_1") (pintype "passive"))
      (node (ref "R67") (pin "2") (pinfunction "2_2") (pintype "passive"))
      (node (ref "U16") (pin "2") (pinfunction "-IN_2") (pintype "input"))
    )
    (net (code "122") (name "Net-(U16--VS)") (class "Default")
      (node (ref "C77") (pin "2") (pinfunction "2_2") (pintype "passive"))
      (node (ref "C78") (pin "2") (pinfunction "2_2") (pintype "passive"))
      (node (ref "R57") (pin "1") (pinfunction "1_1") (pintype "passive"))
      (node (ref "U16") (pin "4") (pinfunction "-VS_4") (pintype "power_in"))
    )
    (net (code "123") (name "Net-(U16-NEU)") (class "Default")
      (node (ref "C83") (pin "2") (pinfunction "2_2") (pintype "passive"))
      (node (ref "U16") (pin "8") (pinfunction "NEU_8") (pintype "power_in"))
    )
    (net (code "124") (name "Net-(U18-OUT+)") (class "Default")
      (node (ref "R63") (pin "1") (pinfunction "1_1") (pintype "passive"))
      (node (ref "U18") (pin "4") (pinfunction "OUT+_4") (pintype "passive"))
    )
    (net (code "125") (name "Net-(U18-OUT-)") (class "Default")
      (node (ref "R64") (pin "1") (pinfunction "1_1") (pintype "passive"))
      (node (ref "U18") (pin "5") (pinfunction "OUT-_5") (pintype "passive"))
    )
    (net (code "126") (name "Net-(U19-+IN)") (class "Default")
      (node (ref "C97") (pin "2") (pinfunction "2_2") (pintype "passive"))
      (node (ref "R71") (pin "2") (pinfunction "2_2") (pintype "passive"))
      (node (ref "U19") (pin "3") (pinfunction "+IN_3") (pintype "input"))
    )
    (net (code "127") (name "Net-(U19--IN)") (class "Default")
      (node (ref "R62") (pin "1") (pinfunction "1_1") (pintype "passive"))
      (node (ref "U19") (pin "2") (pinfunction "-IN_2") (pintype "input"))
    )
    (net (code "128") (name "Net-(U19--VS)") (class "Default")
      (node (ref "C86") (pin "2") (pinfunction "2_2") (pintype "passive"))
      (node (ref "C87") (pin "2") (pinfunction "2_2") (pintype "passive"))
      (node (ref "R61") (pin "1") (pinfunction "1_1") (pintype "passive"))
      (node (ref "U19") (pin "4") (pinfunction "-VS_4") (pintype "power_in"))
    )
    (net (code "129") (name "Net-(U19-NEU)") (class "Default")
      (node (ref "C94") (pin "2") (pinfunction "2_2") (pintype "passive"))
      (node (ref "U19") (pin "8") (pinfunction "NEU_8") (pintype "power_in"))
    )
    (net (code "130") (name "unconnected-(D3-Pad1)") (class "Default")
      (node (ref "D3") (pin "1") (pintype "passive+no_connect"))
    )
    (net (code "131") (name "unconnected-(D4-Pad1)") (class "Default")
      (node (ref "D4") (pin "1") (pintype "passive+no_connect"))
    )
    (net (code "132") (name "unconnected-(D5-Pad1)") (class "Default")
      (node (ref "D5") (pin "1") (pintype "passive+no_connect"))
    )
    (net (code "133") (name "unconnected-(D6-NC-Pad1)") (class "Default")
      (node (ref "D6") (pin "1") (pinfunction "NC_1") (pintype "passive+no_connect"))
    )
    (net (code "134") (name "unconnected-(D7-NC-Pad1)") (class "Default")
      (node (ref "D7") (pin "1") (pinfunction "NC_1") (pintype "passive+no_connect"))
    )
    (net (code "135") (name "unconnected-(D8-NC-Pad1)") (class "Default")
      (node (ref "D8") (pin "1") (pinfunction "NC_1") (pintype "passive+no_connect"))
    )
    (net (code "136") (name "unconnected-(D9-NC-Pad1)") (class "Default")
      (node (ref "D9") (pin "1") (pinfunction "NC_1") (pintype "passive+no_connect"))
    )
    (net (code "137") (name "unconnected-(D10-NC-Pad1)") (class "Default")
      (node (ref "D10") (pin "1") (pinfunction "NC_1") (pintype "passive+no_connect"))
    )
    (net (code "138") (name "unconnected-(D11-NC-Pad1)") (class "Default")
      (node (ref "D11") (pin "1") (pinfunction "NC_1") (pintype "passive+no_connect"))
    )
    (net (code "139") (name "unconnected-(D14-Pad1)") (class "Default")
      (node (ref "D14") (pin "1") (pintype "passive+no_connect"))
    )
    (net (code "140") (name "unconnected-(D15-Pad1)") (class "Default")
      (node (ref "D15") (pin "1") (pintype "passive+no_connect"))
    )
    (net (code "141") (name "unconnected-(D16-Pad1)") (class "Default")
      (node (ref "D16") (pin "1") (pintype "passive+no_connect"))
    )
    (net (code "142") (name "unconnected-(D17-Pad1)") (class "Default")
      (node (ref "D17") (pin "1") (pintype "passive+no_connect"))
    )
    (net (code "143") (name "unconnected-(D34-NC-Pad1)") (class "Default")
      (node (ref "D34") (pin "1") (pinfunction "NC_1") (pintype "passive"))
    )
    (net (code "144") (name "unconnected-(D35-NC-Pad1)") (class "Default")
      (node (ref "D35") (pin "1") (pinfunction "NC_1") (pintype "passive"))
    )
    (net (code "145") (name "unconnected-(D36-NC-Pad1)") (class "Default")
      (node (ref "D36") (pin "1") (pinfunction "NC_1") (pintype "passive"))
    )
    (net (code "146") (name "unconnected-(D37-NC-Pad1)") (class "Default")
      (node (ref "D37") (pin "1") (pinfunction "NC_1") (pintype "passive"))
    )
    (net (code "147") (name "unconnected-(U1-INB+-Pad14)") (class "Default")
      (node (ref "U1") (pin "14") (pinfunction "INB+_14") (pintype "passive+no_connect"))
    )
    (net (code "148") (name "unconnected-(U1-INB--Pad15)") (class "Default")
      (node (ref "U1") (pin "15") (pinfunction "INB-_15") (pintype "passive+no_connect"))
    )
    (net (code "149") (name "unconnected-(U1-IND+-Pad10)") (class "Default")
      (node (ref "U1") (pin "10") (pinfunction "IND+_10") (pintype "passive+no_connect"))
    )
    (net (code "150") (name "unconnected-(U1-IND--Pad9)") (class "Default")
      (node (ref "U1") (pin "9") (pinfunction "IND-_9") (pintype "passive+no_connect"))
    )
    (net (code "151") (name "unconnected-(U1-OUB-Pad13)") (class "Default")
      (node (ref "U1") (pin "13") (pinfunction "OUB_13") (pintype "passive+no_connect"))
    )
    (net (code "152") (name "unconnected-(U1-OUTD-Pad11)") (class "Default")
      (node (ref "U1") (pin "11") (pinfunction "OUTD_11") (pintype "passive+no_connect"))
    )
    (net (code "153") (name "unconnected-(U2B-~{O}-Pad6)") (class "Default")
      (node (ref "U2") (pin "6") (pinfunction "~{O}_6") (pintype "output+no_connect"))
    )
    (net (code "154") (name "unconnected-(U3A-~{O}-Pad2)") (class "Default")
      (node (ref "U3") (pin "2") (pinfunction "~{O}_2") (pintype "output+no_connect"))
    )
    (net (code "155") (name "unconnected-(U3B-~{O}-Pad4)") (class "Default")
      (node (ref "U3") (pin "4") (pinfunction "~{O}_4") (pintype "output+no_connect"))
    )
    (net (code "156") (name "unconnected-(U3D-~{O}-Pad12)") (class "Default")
      (node (ref "U3") (pin "12") (pinfunction "~{O}_12") (pintype "output+no_connect"))
    )
    (net (code "157") (name "unconnected-(U5-NC-Pad3)") (class "Default")
      (node (ref "U5") (pin "3") (pinfunction "NC_3") (pintype "passive+no_connect"))
    )
    (net (code "158") (name "unconnected-(U6-NC-Pad3)") (class "Default")
      (node (ref "U6") (pin "3") (pinfunction "NC_3") (pintype "passive+no_connect"))
    )
    (net (code "159") (name "unconnected-(U7-NC-Pad3)") (class "Default")
      (node (ref "U7") (pin "3") (pinfunction "NC_3") (pintype "passive+no_connect"))
    )
    (net (code "160") (name "unconnected-(U8-NC-Pad3)") (class "Default")
      (node (ref "U8") (pin "3") (pinfunction "NC_3") (pintype "passive+no_connect"))
    )
    (net (code "161") (name "unconnected-(U10-NC-Pad5)") (class "Default")
      (node (ref "U10") (pin "5") (pinfunction "NC_5") (pintype "power_in+no_connect"))
    )
    (net (code "162") (name "unconnected-(U10-Pad1)") (class "Default")
      (node (ref "U10") (pin "1") (pinfunction "1_1") (pintype "power_in+no_connect"))
    )
    (net (code "163") (name "unconnected-(U11-NC-Pad5)") (class "Default")
      (node (ref "U11") (pin "5") (pinfunction "NC_5") (pintype "power_in+no_connect"))
    )
    (net (code "164") (name "unconnected-(U11-Pad1)") (class "Default")
      (node (ref "U11") (pin "1") (pinfunction "1_1") (pintype "power_in+no_connect"))
    )
    (net (code "165") (name "unconnected-(U12-NC-Pad5)") (class "Default")
      (node (ref "U12") (pin "5") (pinfunction "NC_5") (pintype "power_in+no_connect"))
    )
    (net (code "166") (name "unconnected-(U12-Pad1)") (class "Default")
      (node (ref "U12") (pin "1") (pinfunction "1_1") (pintype "power_in+no_connect"))
    )
    (net (code "167") (name "unconnected-(U13-NC-Pad5)") (class "Default")
      (node (ref "U13") (pin "5") (pinfunction "NC_5") (pintype "power_in+no_connect"))
    )
    (net (code "168") (name "unconnected-(U13-Pad1)") (class "Default")
      (node (ref "U13") (pin "1") (pinfunction "1_1") (pintype "power_in+no_connect"))
    )
    (net (code "169") (name "unconnected-(U16-NC-Pad5)") (class "Default")
      (node (ref "U16") (pin "5") (pinfunction "NC_5") (pintype "power_in+no_connect"))
    )
    (net (code "170") (name "unconnected-(U16-Pad1)") (class "Default")
      (node (ref "U16") (pin "1") (pinfunction "1_1") (pintype "power_in+no_connect"))
    )
    (net (code "171") (name "unconnected-(U18-NC-Pad7)") (class "Default")
      (node (ref "U18") (pin "7") (pinfunction "NC_7") (pintype "passive+no_connect"))
    )
    (net (code "172") (name "unconnected-(U19-NC-Pad5)") (class "Default")
      (node (ref "U19") (pin "5") (pinfunction "NC_5") (pintype "power_in+no_connect"))
    )
    (net (code "173") (name "unconnected-(U19-Pad1)") (class "Default")
      (node (ref "U19") (pin "1") (pinfunction "1_1") (pintype "power_in+no_connect"))
    )
  )
)
